# A1-A2_Switches_new.net
KiCad netlist of a schematic drawn in Altium Designer
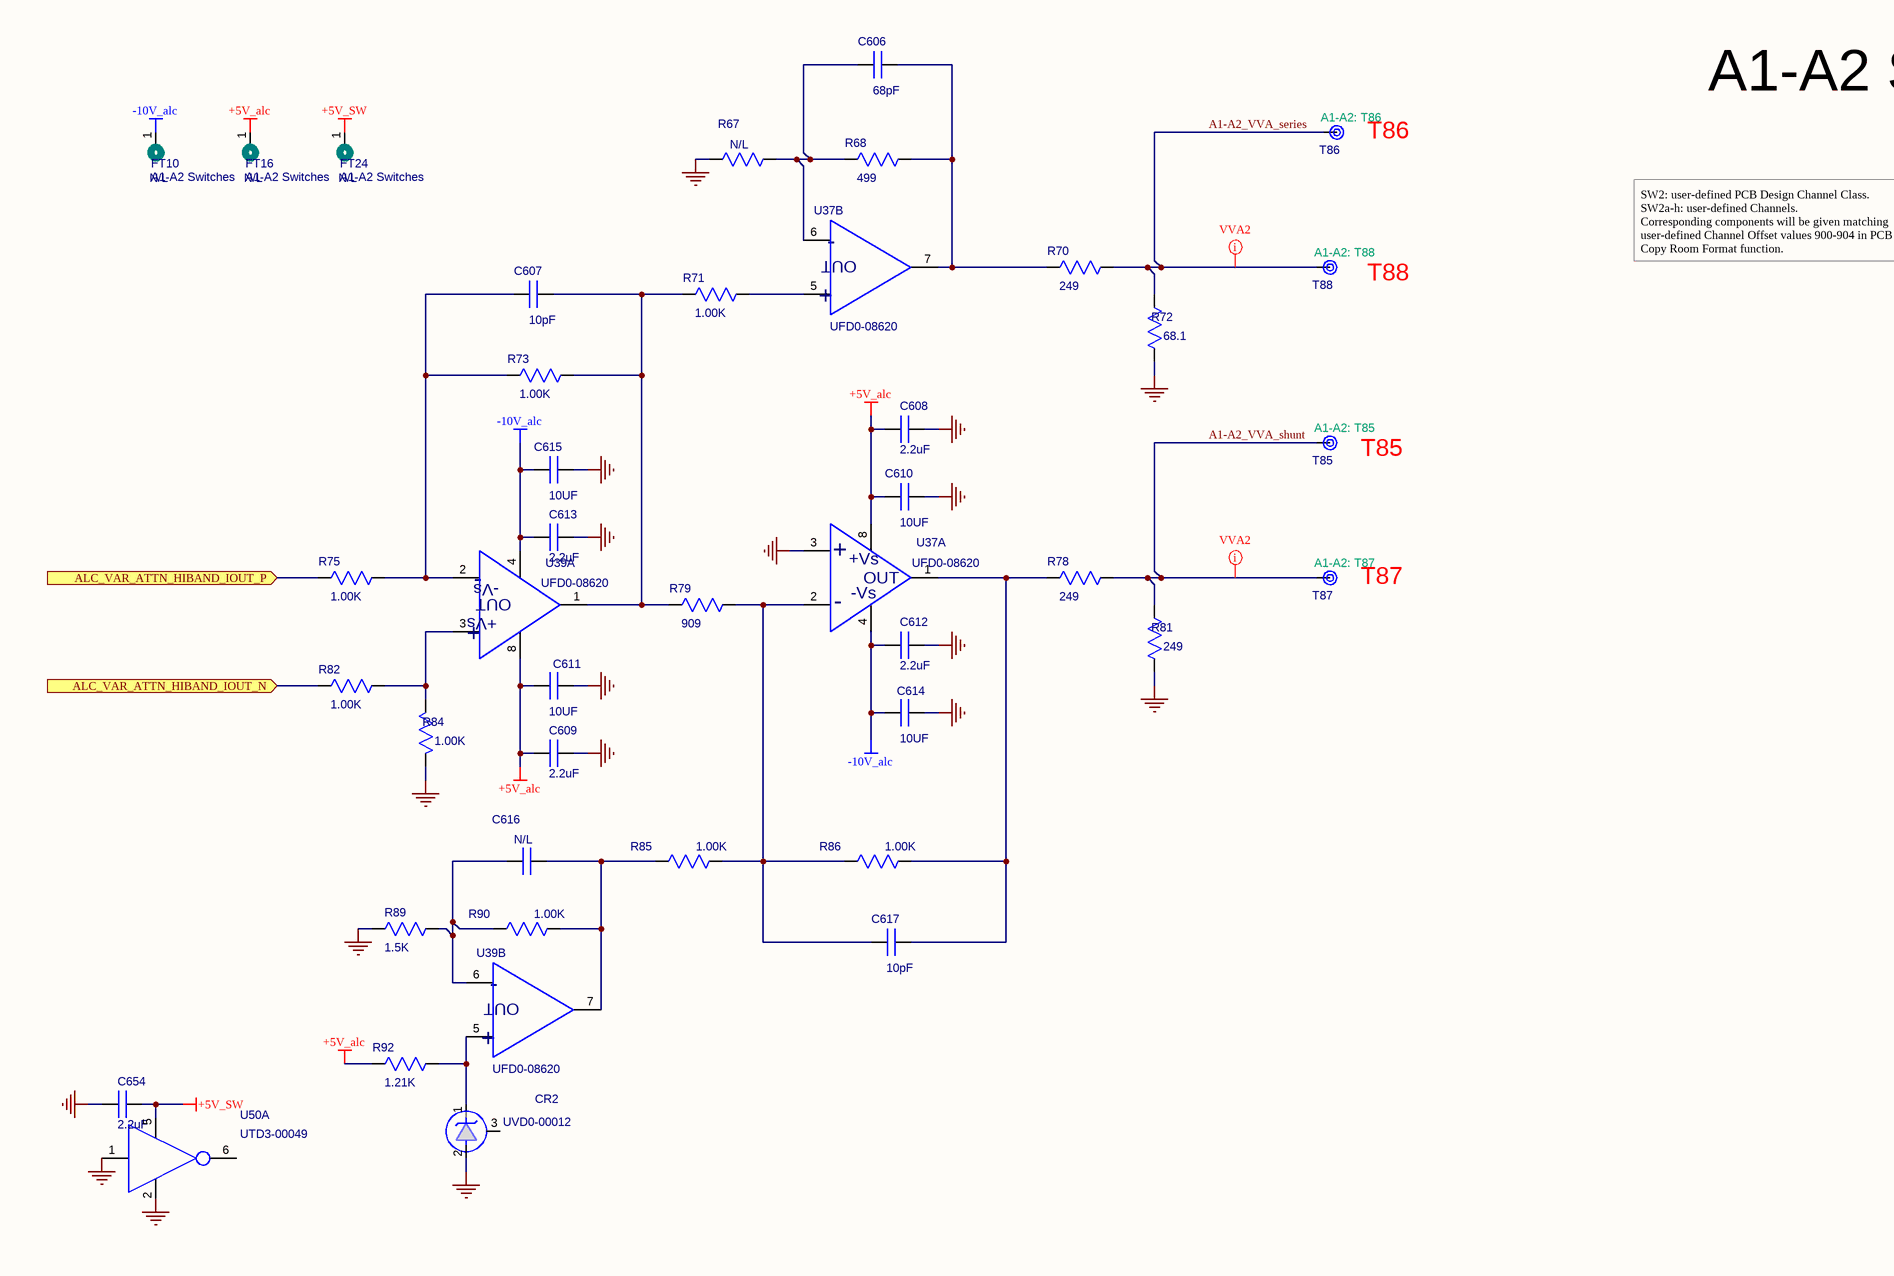
[diagram p0: A1-A2 Switches new.SchDoc, top left]
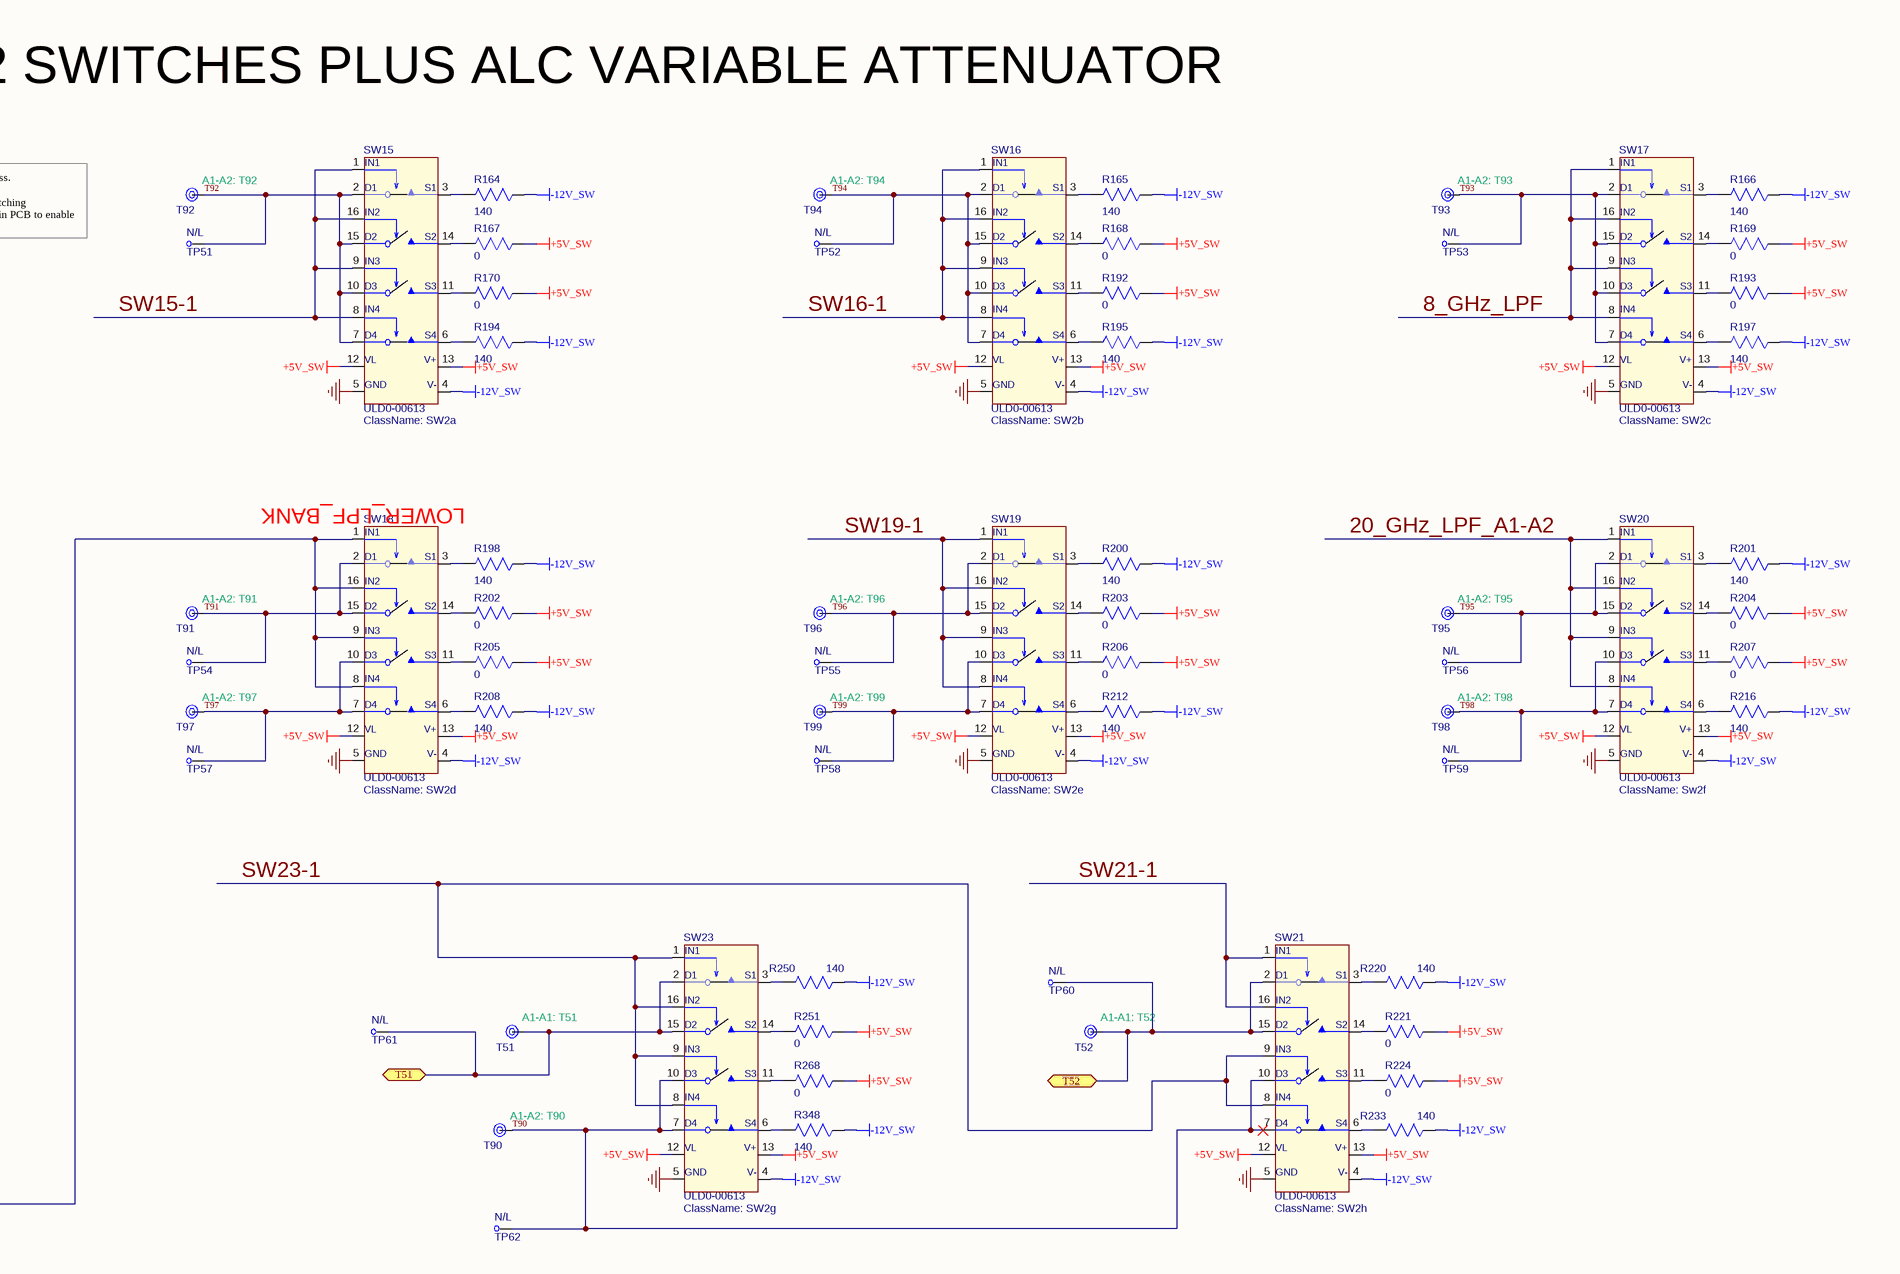
[diagram p1: A1-A2 Switches new.SchDoc, top right]
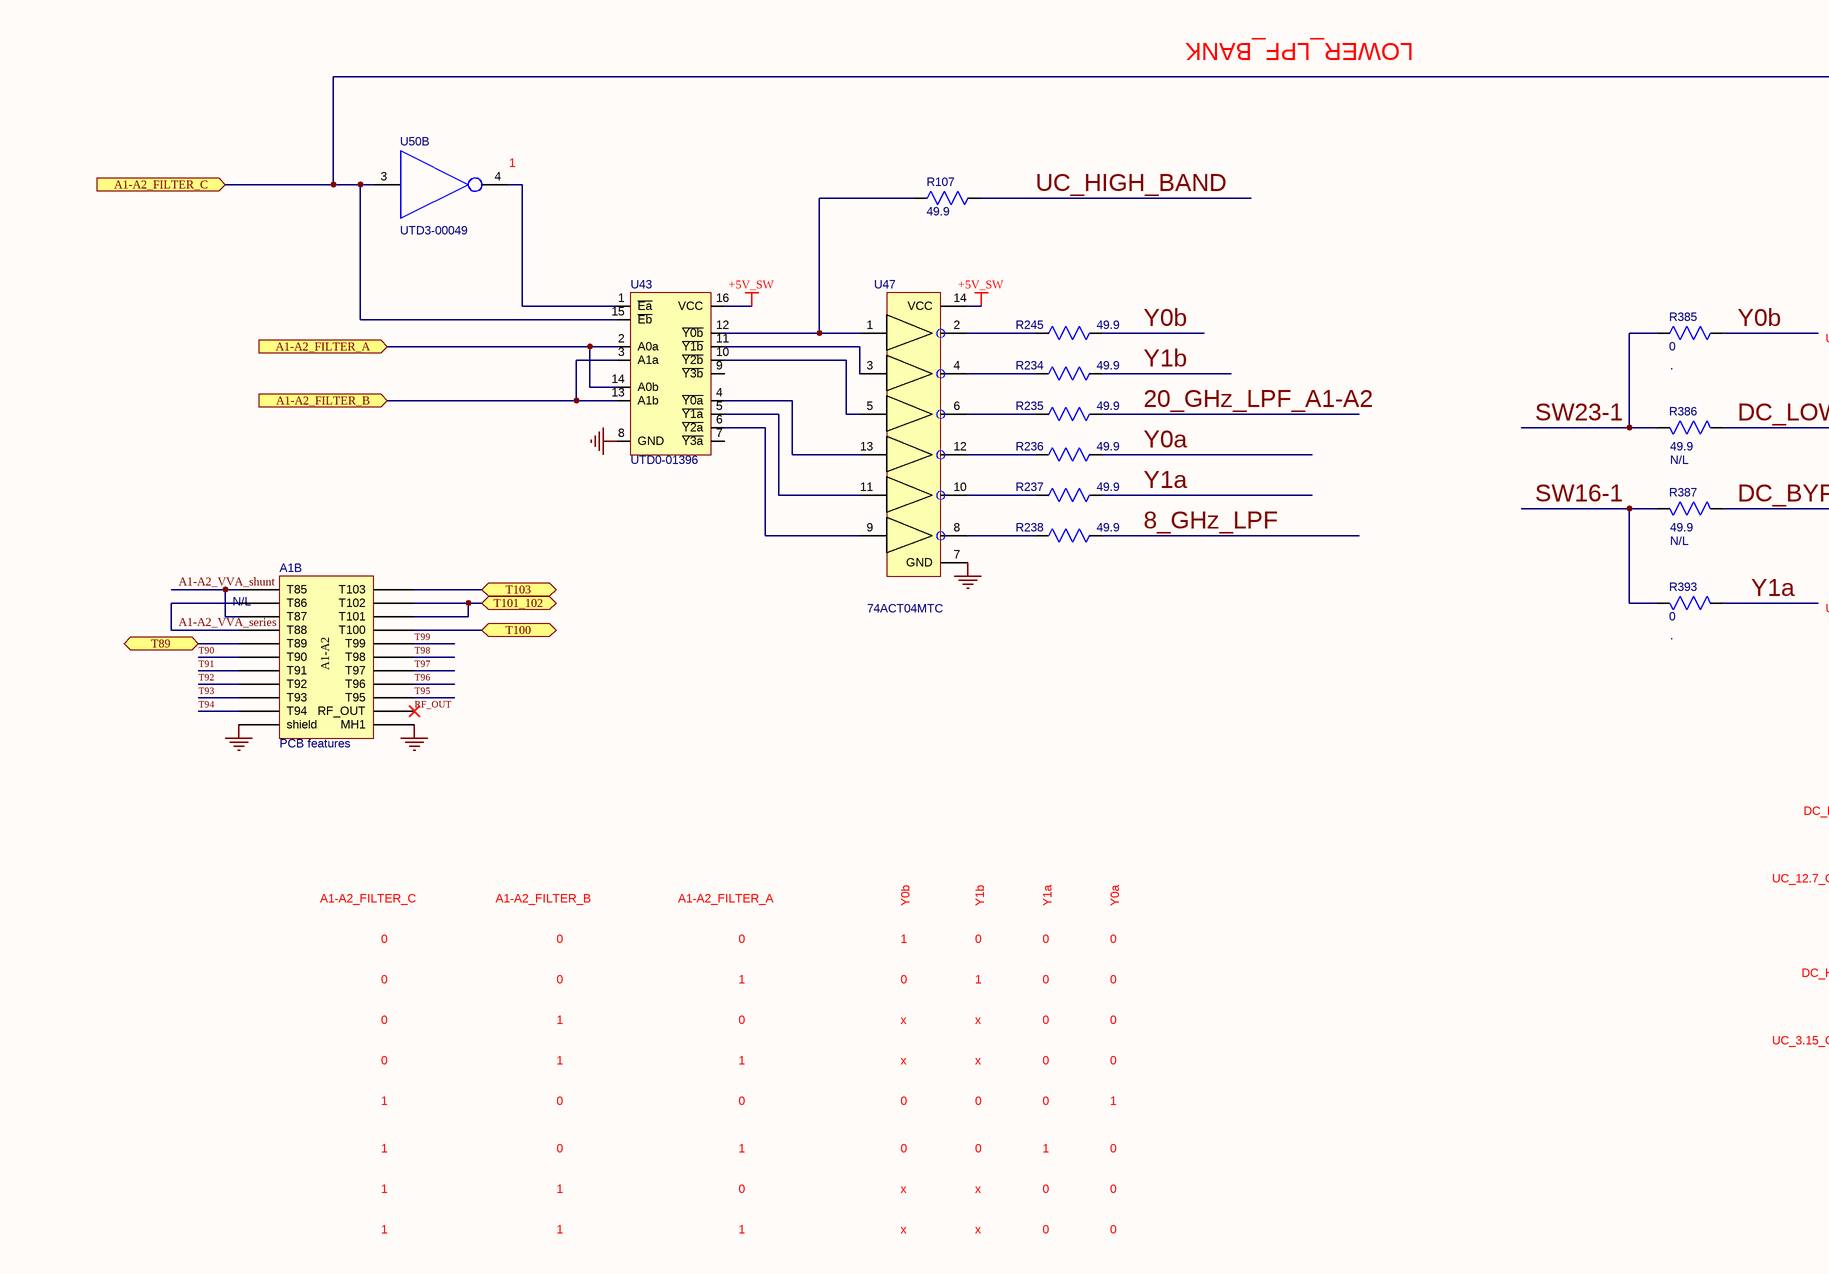
[diagram p2: A1-A2 Switches new.SchDoc, bottom left]
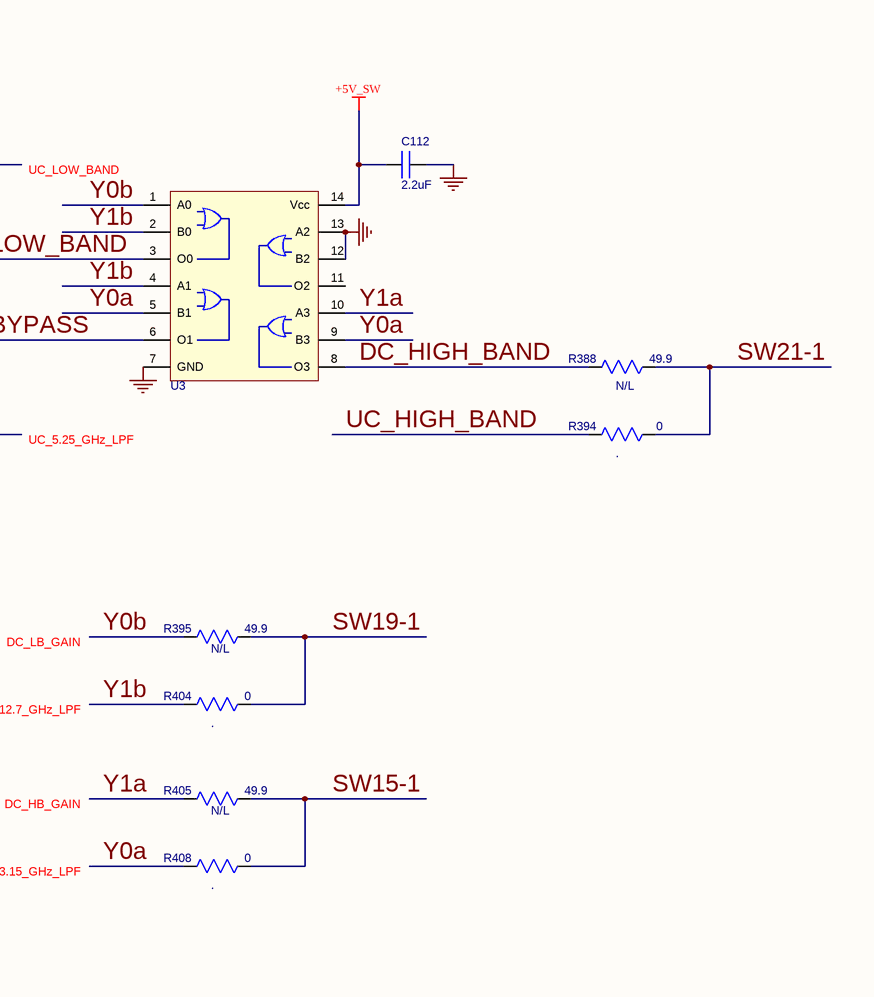
[diagram p3: A1-A2 Switches new.SchDoc, bottom right]

(export (version "E")
  (design (tool "Eeschema 10.0.6"))
  (components
    (comp (ref "A1")
      (value "PCB features")
      (footprint "Hydra_A1_output_modules")
      (description "Hydra A1 output modules (PCB features)")
      (fields (field (name "NOLOAD") "N/L") (field (name "APPROVED") "*"))
      (libsource (lib "Giga-tronics") (part "Hydra A1 output modules"))
    )
    (comp (ref "C112")
      (value "2.2uF")
      (footprint "CAP-0603-H035-N")
      (description "CAP,CHP,2.2UF,10%,X5R;16V")
      (fields (field (name "APPROVED") "CL"))
      (libsource (lib "Giga-tronics") (part "CK45-05220"))
    )
    (comp (ref "C606")
      (value "68pF")
      (footprint "CAP-0402-N")
      (description "68pF;5%;COG;50V;CHIP;0402")
      (fields (field (name "APPROVED") "CL"))
      (libsource (lib "Giga-tronics") (part "CK40-00680"))
    )
    (comp (ref "C607")
      (value "10pF")
      (footprint "CAP-0402-N")
      (description "10 PF;5%;COG;>50V;CHIP;0402")
      (fields (field (name "APPROVED") "CL"))
      (libsource (lib "Giga-tronics") (part "CK40-00100"))
    )
    (comp (ref "C608")
      (value "2.2uF")
      (footprint "CAP-0603-H035-N")
      (description "CAP,CHP,2.2UF,10%,X5R;16V")
      (fields (field (name "APPROVED") "CL"))
      (libsource (lib "Giga-tronics") (part "CK45-05220"))
    )
    (comp (ref "C609")
      (value "2.2uF")
      (footprint "CAP-0603-H035-N")
      (description "CAP,CHP,2.2UF,10%,X5R;16V")
      (fields (field (name "APPROVED") "CL"))
      (libsource (lib "Giga-tronics") (part "CK45-05220"))
    )
    (comp (ref "C610")
      (value "10UF")
      (footprint "CAP-1210-N")
      (description "10uF 10% X7R CERAMIC 16V 1210 CHIP")
      (fields (field (name "APPROVED") "XiaoXiao"))
      (libsource (lib "Giga-tronics") (part "CK60-06100"))
    )
    (comp (ref "C611")
      (value "10UF")
      (footprint "CAP-1210-N")
      (description "10uF 10% X7R CERAMIC 16V 1210 CHIP")
      (fields (field (name "APPROVED") "XiaoXiao"))
      (libsource (lib "Giga-tronics") (part "CK60-06100"))
    )
    (comp (ref "C612")
      (value "2.2uF")
      (footprint "CAP-0603-H035-N")
      (description "CAP,CHP,2.2UF,10%,X5R;16V")
      (fields (field (name "APPROVED") "CL"))
      (libsource (lib "Giga-tronics") (part "CK45-05220"))
    )
    (comp (ref "C613")
      (value "2.2uF")
      (footprint "CAP-0603-H035-N")
      (description "CAP,CHP,2.2UF,10%,X5R;16V")
      (fields (field (name "APPROVED") "CL"))
      (libsource (lib "Giga-tronics") (part "CK45-05220"))
    )
    (comp (ref "C614")
      (value "10UF")
      (footprint "CAP-1210-N")
      (description "10uF 10% X7R CERAMIC 16V 1210 CHIP")
      (fields (field (name "APPROVED") "XiaoXiao"))
      (libsource (lib "Giga-tronics") (part "CK60-06100"))
    )
    (comp (ref "C615")
      (value "10UF")
      (footprint "CAP-1210-N")
      (description "10uF 10% X7R CERAMIC 16V 1210 CHIP")
      (fields (field (name "APPROVED") "XiaoXiao"))
      (libsource (lib "Giga-tronics") (part "CK60-06100"))
    )
    (comp (ref "C616")
      (value "2.2pF;5%;COG;50V;CHIP;0402")
      (footprint "CAP-0402-N")
      (fields (field (name "NOLOAD") "N/L") (field (name "APPROVED") "CL"))
      (libsource (lib "Giga-tronics") (part "CK40-00022"))
    )
    (comp (ref "C617")
      (value "10pF")
      (footprint "CAP-0402-N")
      (description "10 PF;5%;COG;>50V;CHIP;0402")
      (fields (field (name "APPROVED") "CL"))
      (libsource (lib "Giga-tronics") (part "CK40-00100"))
    )
    (comp (ref "C654")
      (value "2.2uF")
      (footprint "CAP-0603-H035-N")
      (description "CAP,CHP,2.2UF,10%,X5R;16V")
      (fields (field (name "APPROVED") "CL"))
      (libsource (lib "Giga-tronics") (part "CK45-05220"))
    )
    (comp (ref "CR2")
      (value "VREF;1.235V;+/-4MV;.2MV 0-70 DEG C;SOT-23")
      (footprint "SOT23-N")
      (fields (field (name "G_PN") "UVD0-00012") (field (name "APPROVED") "CL"))
      (libsource (lib "Giga-tronics") (part "UVD0-00012"))
    )
    (comp (ref "FT10")
      (value "A1-A2 Switches")
      (footprint "FromToNode_ML2")
      (fields (field (name "NOLOAD") "N/L") (field (name "APPROVED") "*"))
      (libsource (lib "Giga-tronics") (part "FromToNode"))
    )
    (comp (ref "FT16")
      (value "A1-A2 Switches")
      (footprint "FromToNode_ML2")
      (fields (field (name "NOLOAD") "N/L") (field (name "APPROVED") "*"))
      (libsource (lib "Giga-tronics") (part "FromToNode"))
    )
    (comp (ref "FT24")
      (value "A1-A2 Switches")
      (footprint "FromToNode_ML2")
      (fields (field (name "NOLOAD") "N/L") (field (name "APPROVED") "*"))
      (libsource (lib "Giga-tronics") (part "FromToNode"))
    )
    (comp (ref "R67")
      (value "32.4K OHMS;.06W;1%;200PPM;FILM;CHIP;0402")
      (footprint "RES-0402-N")
      (fields (field (name "NOLOAD") "N/L") (field (name "APPROVED") "CL"))
      (libsource (lib "Giga-tronics") (part "RK35-23240"))
    )
    (comp (ref "R68")
      (value "499")
      (footprint "RES-0402-N")
      (description "499 OHMS; 1%; .1W; 100PPM; FILM; CHIP; 0402")
      (fields (field (name "APPROVED") "CL"))
      (libsource (lib "Giga-tronics") (part "RK35-04990"))
    )
    (comp (ref "R70")
      (value "249")
      (footprint "RES-0402-N")
      (description "249 OHMS; 1%; .1W; 100PPM; FILM; CHIP; 0402")
      (fields (field (name "APPROVED") "CL"))
      (libsource (lib "Giga-tronics") (part "RK35-02490"))
    )
    (comp (ref "R71")
      (value "1.00K")
      (footprint "RES-0402-N")
      (description "1.0K OHMS;.06W;1%;200PPM;FILM;CHIP;0402")
      (fields (field (name "APPROVED") "CL"))
      (libsource (lib "Giga-tronics") (part "RK35-11000"))
    )
    (comp (ref "R72")
      (value "68.1")
      (footprint "RES-0402-N")
      (description "68.1 OHMS;.06W;1%;200PPM;FILM;CHIP;0402")
      (fields (field (name "APPROVED") "CL"))
      (libsource (lib "Giga-tronics") (part "RK35-00681"))
    )
    (comp (ref "R73")
      (value "1.00K")
      (footprint "RES-0402-N")
      (description "1.0K OHMS;.06W;1%;200PPM;FILM;CHIP;0402")
      (fields (field (name "APPROVED") "CL"))
      (libsource (lib "Giga-tronics") (part "RK35-11000"))
    )
    (comp (ref "R75")
      (value "1.00K")
      (footprint "RES-0402-N")
      (description "1.0K OHMS;.06W;1%;200PPM;FILM;CHIP;0402")
      (fields (field (name "APPROVED") "CL"))
      (libsource (lib "Giga-tronics") (part "RK35-11000"))
    )
    (comp (ref "R78")
      (value "249")
      (footprint "RES-0402-N")
      (description "249 OHMS; 1%; .1W; 100PPM; FILM; CHIP; 0402")
      (fields (field (name "APPROVED") "CL"))
      (libsource (lib "Giga-tronics") (part "RK35-02490"))
    )
    (comp (ref "R79")
      (value "909")
      (footprint "RES-0402-N")
      (description "909 OHMS; 1%; .1W; 100PPM; FILM; CHIP; 0402")
      (fields (field (name "APPROVED") "CL"))
      (libsource (lib "Giga-tronics") (part "RK35-09090"))
    )
    (comp (ref "R81")
      (value "249")
      (footprint "RES-0402-N")
      (description "249 OHMS; 1%; .1W; 100PPM; FILM; CHIP; 0402")
      (fields (field (name "APPROVED") "CL"))
      (libsource (lib "Giga-tronics") (part "RK35-02490"))
    )
    (comp (ref "R82")
      (value "1.00K")
      (footprint "RES-0402-N")
      (description "1.0K OHMS;.06W;1%;200PPM;FILM;CHIP;0402")
      (fields (field (name "APPROVED") "CL"))
      (libsource (lib "Giga-tronics") (part "RK35-11000"))
    )
    (comp (ref "R84")
      (value "1.00K")
      (footprint "RES-0402-N")
      (description "1.0K OHMS;.06W;1%;200PPM;FILM;CHIP;0402")
      (fields (field (name "APPROVED") "CL"))
      (libsource (lib "Giga-tronics") (part "RK35-11000"))
    )
    (comp (ref "R85")
      (value "1.00K")
      (footprint "RES-0402-N")
      (description "1.0K OHMS;.06W;1%;200PPM;FILM;CHIP;0402")
      (fields (field (name "APPROVED") "CL"))
      (libsource (lib "Giga-tronics") (part "RK35-11000"))
    )
    (comp (ref "R86")
      (value "1.00K")
      (footprint "RES-0402-N")
      (description "1.0K OHMS;.06W;1%;200PPM;FILM;CHIP;0402")
      (fields (field (name "APPROVED") "CL"))
      (libsource (lib "Giga-tronics") (part "RK35-11000"))
    )
    (comp (ref "R89")
      (value "1.5K")
      (footprint "RES-0402-N")
      (description "1.50K Ohms;.06W;1%;±100PPM;CHIP RES;0402")
      (fields (field (name "APPROVED") "CL"))
      (libsource (lib "Giga-tronics") (part "RK35-11500"))
    )
    (comp (ref "R90")
      (value "1.00K")
      (footprint "RES-0402-N")
      (description "1.0K OHMS;.06W;1%;200PPM;FILM;CHIP;0402")
      (fields (field (name "APPROVED") "CL"))
      (libsource (lib "Giga-tronics") (part "RK35-11000"))
    )
    (comp (ref "R92")
      (value "1.21K")
      (footprint "RES-0402-N")
      (description "1.21K OHMS;.06W;1%;200PPM;FILM;CHIP;0402")
      (fields (field (name "APPROVED") "CL"))
      (libsource (lib "Giga-tronics") (part "RK35-11210"))
    )
    (comp (ref "R107")
      (value "49.9")
      (footprint "RES-0402-N")
      (description "49.9 OHMS;.06W;1%;200PPM;FILM;CHIP;0402")
      (fields (field (name "APPROVED") "CL"))
      (libsource (lib "Giga-tronics") (part "RK35-00499"))
    )
    (comp (ref "R164")
      (value "140")
      (footprint "RES-0402-N")
      (description "140 OHMS; 1%; .1W; 100PPM; FILM; CHIP; 0402")
      (fields (field (name "APPROVED") "CL"))
      (libsource (lib "Giga-tronics") (part "RK35-01400"))
    )
    (comp (ref "R165")
      (value "140")
      (footprint "RES-0402-N")
      (description "140 OHMS; 1%; .1W; 100PPM; FILM; CHIP; 0402")
      (fields (field (name "APPROVED") "CL"))
      (libsource (lib "Giga-tronics") (part "RK35-01400"))
    )
    (comp (ref "R166")
      (value "140")
      (footprint "RES-0402-N")
      (description "140 OHMS; 1%; .1W; 100PPM; FILM; CHIP; 0402")
      (fields (field (name "APPROVED") "CL"))
      (libsource (lib "Giga-tronics") (part "RK35-01400"))
    )
    (comp (ref "R167")
      (value "0")
      (footprint "RES-0603-N")
      (description "JUMPER;.05 OHMS MAX;1A MAX;0603")
      (fields (field (name "APPROVED") "CL"))
      (libsource (lib "Giga-tronics") (part "RK40-00000"))
    )
    (comp (ref "R168")
      (value "0")
      (footprint "RES-0603-N")
      (description "JUMPER;.05 OHMS MAX;1A MAX;0603")
      (fields (field (name "APPROVED") "CL"))
      (libsource (lib "Giga-tronics") (part "RK40-00000"))
    )
    (comp (ref "R169")
      (value "0")
      (footprint "RES-0603-N")
      (description "JUMPER;.05 OHMS MAX;1A MAX;0603")
      (fields (field (name "APPROVED") "CL"))
      (libsource (lib "Giga-tronics") (part "RK40-00000"))
    )
    (comp (ref "R170")
      (value "0")
      (footprint "RES-0603-N")
      (description "JUMPER;.05 OHMS MAX;1A MAX;0603")
      (fields (field (name "APPROVED") "CL"))
      (libsource (lib "Giga-tronics") (part "RK40-00000"))
    )
    (comp (ref "R192")
      (value "0")
      (footprint "RES-0603-N")
      (description "JUMPER;.05 OHMS MAX;1A MAX;0603")
      (fields (field (name "APPROVED") "CL"))
      (libsource (lib "Giga-tronics") (part "RK40-00000"))
    )
    (comp (ref "R193")
      (value "0")
      (footprint "RES-0603-N")
      (description "JUMPER;.05 OHMS MAX;1A MAX;0603")
      (fields (field (name "APPROVED") "CL"))
      (libsource (lib "Giga-tronics") (part "RK40-00000"))
    )
    (comp (ref "R194")
      (value "140")
      (footprint "RES-0402-N")
      (description "140 OHMS; 1%; .1W; 100PPM; FILM; CHIP; 0402")
      (fields (field (name "APPROVED") "CL"))
      (libsource (lib "Giga-tronics") (part "RK35-01400"))
    )
    (comp (ref "R195")
      (value "140")
      (footprint "RES-0402-N")
      (description "140 OHMS; 1%; .1W; 100PPM; FILM; CHIP; 0402")
      (fields (field (name "APPROVED") "CL"))
      (libsource (lib "Giga-tronics") (part "RK35-01400"))
    )
    (comp (ref "R197")
      (value "140")
      (footprint "RES-0402-N")
      (description "140 OHMS; 1%; .1W; 100PPM; FILM; CHIP; 0402")
      (fields (field (name "APPROVED") "CL"))
      (libsource (lib "Giga-tronics") (part "RK35-01400"))
    )
    (comp (ref "R198")
      (value "140")
      (footprint "RES-0402-N")
      (description "140 OHMS; 1%; .1W; 100PPM; FILM; CHIP; 0402")
      (fields (field (name "APPROVED") "CL"))
      (libsource (lib "Giga-tronics") (part "RK35-01400"))
    )
    (comp (ref "R200")
      (value "140")
      (footprint "RES-0402-N")
      (description "140 OHMS; 1%; .1W; 100PPM; FILM; CHIP; 0402")
      (fields (field (name "APPROVED") "CL"))
      (libsource (lib "Giga-tronics") (part "RK35-01400"))
    )
    (comp (ref "R201")
      (value "140")
      (footprint "RES-0402-N")
      (description "140 OHMS; 1%; .1W; 100PPM; FILM; CHIP; 0402")
      (fields (field (name "APPROVED") "CL"))
      (libsource (lib "Giga-tronics") (part "RK35-01400"))
    )
    (comp (ref "R202")
      (value "0")
      (footprint "RES-0603-N")
      (description "JUMPER;.05 OHMS MAX;1A MAX;0603")
      (fields (field (name "APPROVED") "CL"))
      (libsource (lib "Giga-tronics") (part "RK40-00000"))
    )
    (comp (ref "R203")
      (value "0")
      (footprint "RES-0603-N")
      (description "JUMPER;.05 OHMS MAX;1A MAX;0603")
      (fields (field (name "APPROVED") "CL"))
      (libsource (lib "Giga-tronics") (part "RK40-00000"))
    )
    (comp (ref "R204")
      (value "0")
      (footprint "RES-0603-N")
      (description "JUMPER;.05 OHMS MAX;1A MAX;0603")
      (fields (field (name "APPROVED") "CL"))
      (libsource (lib "Giga-tronics") (part "RK40-00000"))
    )
    (comp (ref "R205")
      (value "0")
      (footprint "RES-0603-N")
      (description "JUMPER;.05 OHMS MAX;1A MAX;0603")
      (fields (field (name "APPROVED") "CL"))
      (libsource (lib "Giga-tronics") (part "RK40-00000"))
    )
    (comp (ref "R206")
      (value "0")
      (footprint "RES-0603-N")
      (description "JUMPER;.05 OHMS MAX;1A MAX;0603")
      (fields (field (name "APPROVED") "CL"))
      (libsource (lib "Giga-tronics") (part "RK40-00000"))
    )
    (comp (ref "R207")
      (value "0")
      (footprint "RES-0603-N")
      (description "JUMPER;.05 OHMS MAX;1A MAX;0603")
      (fields (field (name "APPROVED") "CL"))
      (libsource (lib "Giga-tronics") (part "RK40-00000"))
    )
    (comp (ref "R208")
      (value "140")
      (footprint "RES-0402-N")
      (description "140 OHMS; 1%; .1W; 100PPM; FILM; CHIP; 0402")
      (fields (field (name "APPROVED") "CL"))
      (libsource (lib "Giga-tronics") (part "RK35-01400"))
    )
    (comp (ref "R212")
      (value "140")
      (footprint "RES-0402-N")
      (description "140 OHMS; 1%; .1W; 100PPM; FILM; CHIP; 0402")
      (fields (field (name "APPROVED") "CL"))
      (libsource (lib "Giga-tronics") (part "RK35-01400"))
    )
    (comp (ref "R216")
      (value "140")
      (footprint "RES-0402-N")
      (description "140 OHMS; 1%; .1W; 100PPM; FILM; CHIP; 0402")
      (fields (field (name "APPROVED") "CL"))
      (libsource (lib "Giga-tronics") (part "RK35-01400"))
    )
    (comp (ref "R220")
      (value "140")
      (footprint "RES-0603-N")
      (description "140 OHMS;.1W;1%;200PPM;FILM;CHIP;0603")
      (fields (field (name "APPROVED") "CL"))
      (libsource (lib "Giga-tronics") (part "RK41-01400"))
    )
    (comp (ref "R221")
      (value "0")
      (footprint "RES-0603-N")
      (description "JUMPER;.05 OHMS MAX;1A MAX;0603")
      (fields (field (name "APPROVED") "CL"))
      (libsource (lib "Giga-tronics") (part "RK40-00000"))
    )
    (comp (ref "R224")
      (value "0")
      (footprint "RES-0603-N")
      (description "JUMPER;.05 OHMS MAX;1A MAX;0603")
      (fields (field (name "APPROVED") "CL"))
      (libsource (lib "Giga-tronics") (part "RK40-00000"))
    )
    (comp (ref "R233")
      (value "140")
      (footprint "RES-0603-N")
      (description "140 OHMS;.1W;1%;200PPM;FILM;CHIP;0603")
      (fields (field (name "APPROVED") "CL"))
      (libsource (lib "Giga-tronics") (part "RK41-01400"))
    )
    (comp (ref "R234")
      (value "49.9")
      (footprint "RES-0402-N")
      (description "49.9 OHMS;.06W;1%;200PPM;FILM;CHIP;0402")
      (fields (field (name "APPROVED") "CL"))
      (libsource (lib "Giga-tronics") (part "RK35-00499"))
    )
    (comp (ref "R235")
      (value "49.9")
      (footprint "RES-0402-N")
      (description "49.9 OHMS;.06W;1%;200PPM;FILM;CHIP;0402")
      (fields (field (name "APPROVED") "CL"))
      (libsource (lib "Giga-tronics") (part "RK35-00499"))
    )
    (comp (ref "R236")
      (value "49.9")
      (footprint "RES-0402-N")
      (description "49.9 OHMS;.06W;1%;200PPM;FILM;CHIP;0402")
      (fields (field (name "APPROVED") "CL"))
      (libsource (lib "Giga-tronics") (part "RK35-00499"))
    )
    (comp (ref "R237")
      (value "49.9")
      (footprint "RES-0402-N")
      (description "49.9 OHMS;.06W;1%;200PPM;FILM;CHIP;0402")
      (fields (field (name "APPROVED") "CL"))
      (libsource (lib "Giga-tronics") (part "RK35-00499"))
    )
    (comp (ref "R238")
      (value "49.9")
      (footprint "RES-0402-N")
      (description "49.9 OHMS;.06W;1%;200PPM;FILM;CHIP;0402")
      (fields (field (name "APPROVED") "CL"))
      (libsource (lib "Giga-tronics") (part "RK35-00499"))
    )
    (comp (ref "R245")
      (value "49.9")
      (footprint "RES-0402-N")
      (description "49.9 OHMS;.06W;1%;200PPM;FILM;CHIP;0402")
      (fields (field (name "APPROVED") "CL"))
      (libsource (lib "Giga-tronics") (part "RK35-00499"))
    )
    (comp (ref "R250")
      (value "140")
      (footprint "RES-0603-N")
      (description "140 OHMS;.1W;1%;200PPM;FILM;CHIP;0603")
      (fields (field (name "APPROVED") "CL"))
      (libsource (lib "Giga-tronics") (part "RK41-01400"))
    )
    (comp (ref "R251")
      (value "0")
      (footprint "RES-0603-N")
      (description "JUMPER;.05 OHMS MAX;1A MAX;0603")
      (fields (field (name "APPROVED") "CL"))
      (libsource (lib "Giga-tronics") (part "RK40-00000"))
    )
    (comp (ref "R268")
      (value "0")
      (footprint "RES-0603-N")
      (description "JUMPER;.05 OHMS MAX;1A MAX;0603")
      (fields (field (name "APPROVED") "CL"))
      (libsource (lib "Giga-tronics") (part "RK40-00000"))
    )
    (comp (ref "R348")
      (value "140")
      (footprint "RES-0402-N")
      (description "140 OHMS; 1%; .1W; 100PPM; FILM; CHIP; 0402")
      (fields (field (name "APPROVED") "CL"))
      (libsource (lib "Giga-tronics") (part "RK35-01400"))
    )
    (comp (ref "R385")
      (value "UC_LOW_BAND")
      (footprint "RES-0402-N")
      (description "JUMPER;0 OHMS;SMT;0402")
      (fields (field (name "NOLOAD") ".") (field (name "ALTIUM_VALUE") "0") (field (name "APPROVED") "CL"))
      (libsource (lib "Giga-tronics") (part "RK35-00000"))
    )
    (comp (ref "R386")
      (value "49.9")
      (footprint "RES-0402-N")
      (description "49.9 OHMS;.06W;1%;200PPM;FILM;CHIP;0402")
      (fields
        (field (name "NOLOAD") "N/L")
        (field (name "Comment") "DC_LOW_BAND")
        (field (name "APPROVED") "CL")
      )
      (libsource (lib "Giga-tronics") (part "RK35-00499"))
    )
    (comp (ref "R387")
      (value "49.9")
      (footprint "RES-0402-N")
      (description "49.9 OHMS;.06W;1%;200PPM;FILM;CHIP;0402")
      (fields
        (field (name "NOLOAD") "N/L")
        (field (name "Comment") "DC_BYPASS")
        (field (name "APPROVED") "CL")
      )
      (libsource (lib "Giga-tronics") (part "RK35-00499"))
    )
    (comp (ref "R388")
      (value "49.9")
      (footprint "RES-0402-N")
      (description "49.9 OHMS;.06W;1%;200PPM;FILM;CHIP;0402")
      (fields
        (field (name "NOLOAD") "N/L")
        (field (name "Comment") "DC_HIGH_BAND")
        (field (name "APPROVED") "CL")
      )
      (libsource (lib "Giga-tronics") (part "RK35-00499"))
    )
    (comp (ref "R393")
      (value "UC_5.25_GHz_LPF")
      (footprint "RES-0402-N")
      (description "JUMPER;0 OHMS;SMT;0402")
      (fields (field (name "NOLOAD") ".") (field (name "ALTIUM_VALUE") "0") (field (name "APPROVED") "CL"))
      (libsource (lib "Giga-tronics") (part "RK35-00000"))
    )
    (comp (ref "R394")
      (value "0")
      (footprint "RES-0402-N")
      (description "JUMPER;0 OHMS;SMT;0402")
      (fields
        (field (name "NOLOAD") ".")
        (field (name "Comment") "UC_HIGH_BAND")
        (field (name "APPROVED") "CL")
      )
      (libsource (lib "Giga-tronics") (part "RK35-00000"))
    )
    (comp (ref "R395")
      (value "DC_LB_GAIN")
      (footprint "RES-0402-N")
      (description "49.9 OHMS;.06W;1%;200PPM;FILM;CHIP;0402")
      (fields
        (field (name "NOLOAD") "N/L")
        (field (name "ALTIUM_VALUE") "49.9")
        (field (name "APPROVED") "CL")
      )
      (libsource (lib "Giga-tronics") (part "RK35-00499"))
    )
    (comp (ref "R404")
      (value "UC_12.7_GHz_LPF")
      (footprint "RES-0402-N")
      (description "JUMPER;0 OHMS;SMT;0402")
      (fields (field (name "NOLOAD") ".") (field (name "ALTIUM_VALUE") "0") (field (name "APPROVED") "CL"))
      (libsource (lib "Giga-tronics") (part "RK35-00000"))
    )
    (comp (ref "R405")
      (value "DC_HB_GAIN")
      (footprint "RES-0402-N")
      (description "49.9 OHMS;.06W;1%;200PPM;FILM;CHIP;0402")
      (fields
        (field (name "NOLOAD") "N/L")
        (field (name "ALTIUM_VALUE") "49.9")
        (field (name "APPROVED") "CL")
      )
      (libsource (lib "Giga-tronics") (part "RK35-00499"))
    )
    (comp (ref "R408")
      (value "UC_3.15_GHz_LPF")
      (footprint "RES-0402-N")
      (description "JUMPER;0 OHMS;SMT;0402")
      (fields (field (name "NOLOAD") ".") (field (name "ALTIUM_VALUE") "0") (field (name "APPROVED") "CL"))
      (libsource (lib "Giga-tronics") (part "RK35-00000"))
    )
    (comp (ref "SW15")
      (value "QUAD SPST ANALOG SW;200NS;45 OHM;SO-16")
      (footprint "SOIC-16_Vishay")
      (fields
        (field (name "G_PN") "ULD0-00613")
        (field (name "CLASSNAME") "SW2a")
        (field (name "APPROVED") "NM")
      )
      (libsource (lib "Giga-tronics") (part "ULD0-00613_1"))
    )
    (comp (ref "SW16")
      (value "QUAD SPST ANALOG SW;200NS;45 OHM;SO-16")
      (footprint "SOIC-16_Vishay")
      (fields
        (field (name "G_PN") "ULD0-00613")
        (field (name "CLASSNAME") "SW2b")
        (field (name "APPROVED") "NM")
      )
      (libsource (lib "Giga-tronics") (part "ULD0-00613_1"))
    )
    (comp (ref "SW17")
      (value "QUAD SPST ANALOG SW;200NS;45 OHM;SO-16")
      (footprint "SOIC-16_Vishay")
      (fields
        (field (name "G_PN") "ULD0-00613")
        (field (name "CLASSNAME") "SW2c")
        (field (name "APPROVED") "NM")
      )
      (libsource (lib "Giga-tronics") (part "ULD0-00613_1"))
    )
    (comp (ref "SW18")
      (value "QUAD SPST ANALOG SW;200NS;45 OHM;SO-16")
      (footprint "SOIC-16_Vishay")
      (fields
        (field (name "G_PN") "ULD0-00613")
        (field (name "CLASSNAME") "SW2d")
        (field (name "APPROVED") "NM")
      )
      (libsource (lib "Giga-tronics") (part "ULD0-00613_1"))
    )
    (comp (ref "SW19")
      (value "QUAD SPST ANALOG SW;200NS;45 OHM;SO-16")
      (footprint "SOIC-16_Vishay")
      (fields
        (field (name "G_PN") "ULD0-00613")
        (field (name "CLASSNAME") "SW2e")
        (field (name "APPROVED") "NM")
      )
      (libsource (lib "Giga-tronics") (part "ULD0-00613_1"))
    )
    (comp (ref "SW20")
      (value "QUAD SPST ANALOG SW;200NS;45 OHM;SO-16")
      (footprint "SOIC-16_Vishay")
      (fields
        (field (name "G_PN") "ULD0-00613")
        (field (name "CLASSNAME") "Sw2f")
        (field (name "APPROVED") "NM")
      )
      (libsource (lib "Giga-tronics") (part "ULD0-00613_1"))
    )
    (comp (ref "SW21")
      (value "QUAD SPST ANALOG SW;200NS;45 OHM;SO-16")
      (footprint "SOIC-16_Vishay")
      (fields
        (field (name "G_PN") "ULD0-00613")
        (field (name "CLASSNAME") "SW2h")
        (field (name "APPROVED") "NM")
      )
      (libsource (lib "Giga-tronics") (part "ULD0-00613_1"))
    )
    (comp (ref "SW23")
      (value "QUAD SPST ANALOG SW;200NS;45 OHM;SO-16")
      (footprint "SOIC-16_Vishay")
      (fields
        (field (name "G_PN") "ULD0-00613")
        (field (name "CLASSNAME") "SW2g")
        (field (name "APPROVED") "NM")
      )
      (libsource (lib "Giga-tronics") (part "ULD0-00613_1"))
    )
    (comp (ref "T51")
      (value "A1-A1: T51")
      (footprint "JIB0-11254")
      (description "SOCKET;SINGLE;.018-.040 ID X .254;OPEN;GLD")
      (fields (field (name "APPROVED") "NM"))
      (libsource (lib "Giga-tronics") (part "JIB0-11254"))
    )
    (comp (ref "T52")
      (value "A1-A1: T52")
      (footprint "JIB0-11254")
      (description "SOCKET;SINGLE;.018-.040 ID X .254;OPEN;GLD")
      (fields (field (name "APPROVED") "NM"))
      (libsource (lib "Giga-tronics") (part "JIB0-11254"))
    )
    (comp (ref "T85")
      (value "A1-A2: T85")
      (footprint "JIB0-11254")
      (description "SOCKET;SINGLE;.018-.040 ID X .254;OPEN;GLD")
      (fields (field (name "APPROVED") "NM"))
      (libsource (lib "Giga-tronics") (part "JIB0-11254"))
    )
    (comp (ref "T86")
      (value "A1-A2: T86")
      (footprint "JIB0-11254")
      (description "SOCKET;SINGLE;.018-.040 ID X .254;OPEN;GLD")
      (fields (field (name "APPROVED") "NM"))
      (libsource (lib "Giga-tronics") (part "JIB0-11254"))
    )
    (comp (ref "T87")
      (value "A1-A2: T87")
      (footprint "JIB0-11254")
      (description "SOCKET;SINGLE;.018-.040 ID X .254;OPEN;GLD")
      (fields (field (name "APPROVED") "NM"))
      (libsource (lib "Giga-tronics") (part "JIB0-11254"))
    )
    (comp (ref "T88")
      (value "A1-A2: T88")
      (footprint "JIB0-11254")
      (description "SOCKET;SINGLE;.018-.040 ID X .254;OPEN;GLD")
      (fields (field (name "APPROVED") "NM"))
      (libsource (lib "Giga-tronics") (part "JIB0-11254"))
    )
    (comp (ref "T90")
      (value "A1-A2: T90")
      (footprint "JIB0-11254")
      (description "SOCKET;SINGLE;.018-.040 ID X .254;OPEN;GLD")
      (fields (field (name "APPROVED") "NM"))
      (libsource (lib "Giga-tronics") (part "JIB0-11254"))
    )
    (comp (ref "T91")
      (value "A1-A2: T91")
      (footprint "JIB0-11254")
      (description "SOCKET;SINGLE;.018-.040 ID X .254;OPEN;GLD")
      (fields (field (name "APPROVED") "NM"))
      (libsource (lib "Giga-tronics") (part "JIB0-11254"))
    )
    (comp (ref "T92")
      (value "A1-A2: T92")
      (footprint "JIB0-11254")
      (description "SOCKET;SINGLE;.018-.040 ID X .254;OPEN;GLD")
      (fields (field (name "APPROVED") "NM"))
      (libsource (lib "Giga-tronics") (part "JIB0-11254"))
    )
    (comp (ref "T93")
      (value "A1-A2: T93")
      (footprint "JIB0-11254")
      (description "SOCKET;SINGLE;.018-.040 ID X .254;OPEN;GLD")
      (fields (field (name "APPROVED") "NM"))
      (libsource (lib "Giga-tronics") (part "JIB0-11254"))
    )
    (comp (ref "T94")
      (value "A1-A2: T94")
      (footprint "JIB0-11254")
      (description "SOCKET;SINGLE;.018-.040 ID X .254;OPEN;GLD")
      (fields (field (name "APPROVED") "NM"))
      (libsource (lib "Giga-tronics") (part "JIB0-11254"))
    )
    (comp (ref "T95")
      (value "A1-A2: T95")
      (footprint "JIB0-11254")
      (description "SOCKET;SINGLE;.018-.040 ID X .254;OPEN;GLD")
      (fields (field (name "APPROVED") "NM"))
      (libsource (lib "Giga-tronics") (part "JIB0-11254"))
    )
    (comp (ref "T96")
      (value "A1-A2: T96")
      (footprint "JIB0-11254")
      (description "SOCKET;SINGLE;.018-.040 ID X .254;OPEN;GLD")
      (fields (field (name "APPROVED") "NM"))
      (libsource (lib "Giga-tronics") (part "JIB0-11254"))
    )
    (comp (ref "T97")
      (value "A1-A2: T97")
      (footprint "JIB0-11254")
      (description "SOCKET;SINGLE;.018-.040 ID X .254;OPEN;GLD")
      (fields (field (name "APPROVED") "NM"))
      (libsource (lib "Giga-tronics") (part "JIB0-11254"))
    )
    (comp (ref "T98")
      (value "A1-A2: T98")
      (footprint "JIB0-11254")
      (description "SOCKET;SINGLE;.018-.040 ID X .254;OPEN;GLD")
      (fields (field (name "APPROVED") "NM"))
      (libsource (lib "Giga-tronics") (part "JIB0-11254"))
    )
    (comp (ref "T99")
      (value "A1-A2: T99")
      (footprint "JIB0-11254")
      (description "SOCKET;SINGLE;.018-.040 ID X .254;OPEN;GLD")
      (fields (field (name "APPROVED") "NM"))
      (libsource (lib "Giga-tronics") (part "JIB0-11254"))
    )
    (comp (ref "TP51")
      (value ".")
      (footprint "TP-060")
      (fields (field (name "NOLOAD") "N/L") (field (name "APPROVED") "NM"))
      (libsource (lib "Giga-tronics") (part "TP-060"))
    )
    (comp (ref "TP52")
      (value ".")
      (footprint "TP-060")
      (fields (field (name "NOLOAD") "N/L") (field (name "APPROVED") "NM"))
      (libsource (lib "Giga-tronics") (part "TP-060"))
    )
    (comp (ref "TP53")
      (value ".")
      (footprint "TP-060")
      (fields (field (name "NOLOAD") "N/L") (field (name "APPROVED") "NM"))
      (libsource (lib "Giga-tronics") (part "TP-060"))
    )
    (comp (ref "TP54")
      (value ".")
      (footprint "TP-060")
      (fields (field (name "NOLOAD") "N/L") (field (name "APPROVED") "NM"))
      (libsource (lib "Giga-tronics") (part "TP-060"))
    )
    (comp (ref "TP55")
      (value ".")
      (footprint "TP-060")
      (fields (field (name "NOLOAD") "N/L") (field (name "APPROVED") "NM"))
      (libsource (lib "Giga-tronics") (part "TP-060"))
    )
    (comp (ref "TP56")
      (value ".")
      (footprint "TP-060")
      (fields (field (name "NOLOAD") "N/L") (field (name "APPROVED") "NM"))
      (libsource (lib "Giga-tronics") (part "TP-060"))
    )
    (comp (ref "TP57")
      (value ".")
      (footprint "TP-060")
      (fields (field (name "NOLOAD") "N/L") (field (name "APPROVED") "NM"))
      (libsource (lib "Giga-tronics") (part "TP-060"))
    )
    (comp (ref "TP58")
      (value ".")
      (footprint "TP-060")
      (fields (field (name "NOLOAD") "N/L") (field (name "APPROVED") "NM"))
      (libsource (lib "Giga-tronics") (part "TP-060"))
    )
    (comp (ref "TP59")
      (value ".")
      (footprint "TP-060")
      (fields (field (name "NOLOAD") "N/L") (field (name "APPROVED") "NM"))
      (libsource (lib "Giga-tronics") (part "TP-060"))
    )
    (comp (ref "TP60")
      (value ".")
      (footprint "TP-060")
      (fields (field (name "NOLOAD") "N/L") (field (name "APPROVED") "NM"))
      (libsource (lib "Giga-tronics") (part "TP-060"))
    )
    (comp (ref "TP61")
      (value ".")
      (footprint "TP-060")
      (fields (field (name "NOLOAD") "N/L") (field (name "APPROVED") "NM"))
      (libsource (lib "Giga-tronics") (part "TP-060"))
    )
    (comp (ref "TP62")
      (value ".")
      (footprint "TP-060")
      (fields (field (name "NOLOAD") "N/L") (field (name "APPROVED") "NM"))
      (libsource (lib "Giga-tronics") (part "TP-060"))
    )
    (comp (ref "U3")
      (value "QUAD 2 IN OR GATES")
      (footprint "TSSOP-14_ON_SEMI")
      (fields (field (name "APPROVED") "CL"))
      (libsource (lib "Giga-tronics") (part "UTD0-00329"))
    )
    (comp (ref "U37")
      (value "OP-AMP;DUAL:PRECISION;LOW CURRENT;LOW NOISE;WIDE")
      (footprint "SO8_MS-012")
      (fields (field (name "G_PN") "UFD0-08620") (field (name "APPROVED") "CL"))
      (libsource (lib "Giga-tronics") (part "UFD0-08620"))
    )
    (comp (ref "U39")
      (value "OP-AMP;DUAL:PRECISION;LOW CURRENT;LOW NOISE;WIDE")
      (footprint "SO8_MS-012")
      (fields (field (name "G_PN") "UFD0-08620") (field (name "APPROVED") "CL"))
      (libsource (lib "Giga-tronics") (part "UFD0-08620"))
    )
    (comp (ref "U43")
      (value "UTD0-01396")
      (footprint "TSSOP-16_ONSEMI")
      (description "2 TO 4 DECODER/DEMULTIPLEXER;74VHC139 LOGIC;SO-16")
      (fields (field (name "G_PN") "UTD0-01396") (field (name "APPROVED") "CL"))
      (libsource (lib "Giga-tronics") (part "UTD0-01396"))
    )
    (comp (ref "U47")
      (value "74ACT04MTC HEX INVERTER;SMT;TSSOP-14")
      (footprint "TSOP65P640X120-14L")
      (fields (field (name "M_PN") "74ACT04MTC") (field (name "APPROVED") "NM"))
      (libsource (lib "Giga-tronics") (part "UTD4-00046"))
    )
    (comp (ref "U50")
      (value "INVERTER;DUAL;1.65-5.5V SUP;2NS TPD;SC70-6")
      (footprint "SOT-363_419B")
      (fields (field (name "G_PN") "UTD3-00049") (field (name "APPROVED") "CL"))
      (libsource (lib "Giga-tronics") (part "UTD3-00049"))
    )
  )
  (nets
    (net (code "1") (name "+5V_SW") (class "Default")
      (node (ref "C112") (pin "1") (pintype "passive"))
      (node (ref "C654") (pin "1") (pintype "passive"))
      (node (ref "FT24") (pin "1") (pinfunction "1_1") (pintype "passive"))
      (node (ref "R167") (pin "2") (pintype "passive"))
      (node (ref "R168") (pin "2") (pintype "passive"))
      (node (ref "R169") (pin "2") (pintype "passive"))
      (node (ref "R170") (pin "2") (pintype "passive"))
      (node (ref "R192") (pin "2") (pintype "passive"))
      (node (ref "R193") (pin "2") (pintype "passive"))
      (node (ref "R202") (pin "2") (pintype "passive"))
      (node (ref "R203") (pin "2") (pintype "passive"))
      (node (ref "R204") (pin "2") (pintype "passive"))
      (node (ref "R205") (pin "2") (pintype "passive"))
      (node (ref "R206") (pin "2") (pintype "passive"))
      (node (ref "R207") (pin "2") (pintype "passive"))
      (node (ref "R221") (pin "2") (pintype "passive"))
      (node (ref "R224") (pin "2") (pintype "passive"))
      (node (ref "R251") (pin "2") (pintype "passive"))
      (node (ref "R268") (pin "2") (pintype "passive"))
      (node (ref "SW15") (pin "12") (pinfunction "VL_12") (pintype "passive"))
      (node (ref "SW15") (pin "13") (pinfunction "V+_13") (pintype "passive"))
      (node (ref "SW16") (pin "12") (pinfunction "VL_12") (pintype "passive"))
      (node (ref "SW16") (pin "13") (pinfunction "V+_13") (pintype "passive"))
      (node (ref "SW17") (pin "12") (pinfunction "VL_12") (pintype "passive"))
      (node (ref "SW17") (pin "13") (pinfunction "V+_13") (pintype "passive"))
      (node (ref "SW18") (pin "12") (pinfunction "VL_12") (pintype "passive"))
      (node (ref "SW18") (pin "13") (pinfunction "V+_13") (pintype "passive"))
      (node (ref "SW19") (pin "12") (pinfunction "VL_12") (pintype "passive"))
      (node (ref "SW19") (pin "13") (pinfunction "V+_13") (pintype "passive"))
      (node (ref "SW20") (pin "12") (pinfunction "VL_12") (pintype "passive"))
      (node (ref "SW20") (pin "13") (pinfunction "V+_13") (pintype "passive"))
      (node (ref "SW21") (pin "12") (pinfunction "VL_12") (pintype "passive"))
      (node (ref "SW21") (pin "13") (pinfunction "V+_13") (pintype "passive"))
      (node (ref "SW23") (pin "12") (pinfunction "VL_12") (pintype "passive"))
      (node (ref "SW23") (pin "13") (pinfunction "V+_13") (pintype "passive"))
      (node (ref "U3") (pin "14") (pinfunction "Vcc_14") (pintype "passive"))
      (node (ref "U43") (pin "16") (pinfunction "VCC_16") (pintype "passive"))
      (node (ref "U47") (pin "14") (pinfunction "VCC_14") (pintype "passive"))
      (node (ref "U50") (pin "5") (pinfunction "V+_5") (pintype "passive"))
    )
    (net (code "2") (name "+5V_alc") (class "Default")
      (node (ref "C608") (pin "1") (pintype "passive"))
      (node (ref "C609") (pin "1") (pintype "passive"))
      (node (ref "C610") (pin "1") (pintype "passive"))
      (node (ref "C611") (pin "1") (pintype "passive"))
      (node (ref "FT16") (pin "1") (pinfunction "1_1") (pintype "passive"))
      (node (ref "R92") (pin "1") (pintype "passive"))
      (node (ref "U37") (pin "8") (pinfunction "V+_8") (pintype "passive"))
      (node (ref "U39") (pin "8") (pinfunction "V+_8") (pintype "passive"))
    )
    (net (code "3") (name "-10V_alc") (class "Default")
      (node (ref "C612") (pin "1") (pintype "passive"))
      (node (ref "C613") (pin "1") (pintype "passive"))
      (node (ref "C614") (pin "1") (pintype "passive"))
      (node (ref "C615") (pin "1") (pintype "passive"))
      (node (ref "FT10") (pin "1") (pinfunction "1_1") (pintype "passive"))
      (node (ref "U37") (pin "4") (pinfunction "V-_4") (pintype "passive"))
      (node (ref "U39") (pin "4") (pinfunction "V-_4") (pintype "passive"))
    )
    (net (code "4") (name "-12V_SW") (class "Default")
      (node (ref "R164") (pin "2") (pintype "passive"))
      (node (ref "R165") (pin "2") (pintype "passive"))
      (node (ref "R166") (pin "2") (pintype "passive"))
      (node (ref "R194") (pin "2") (pintype "passive"))
      (node (ref "R195") (pin "2") (pintype "passive"))
      (node (ref "R197") (pin "2") (pintype "passive"))
      (node (ref "R198") (pin "2") (pintype "passive"))
      (node (ref "R200") (pin "2") (pintype "passive"))
      (node (ref "R201") (pin "2") (pintype "passive"))
      (node (ref "R208") (pin "2") (pintype "passive"))
      (node (ref "R212") (pin "2") (pintype "passive"))
      (node (ref "R216") (pin "2") (pintype "passive"))
      (node (ref "R220") (pin "2") (pintype "passive"))
      (node (ref "R233") (pin "2") (pintype "passive"))
      (node (ref "R250") (pin "2") (pintype "passive"))
      (node (ref "R348") (pin "2") (pintype "passive"))
      (node (ref "SW15") (pin "4") (pinfunction "VL_4") (pintype "passive"))
      (node (ref "SW16") (pin "4") (pinfunction "VL_4") (pintype "passive"))
      (node (ref "SW17") (pin "4") (pinfunction "VL_4") (pintype "passive"))
      (node (ref "SW18") (pin "4") (pinfunction "VL_4") (pintype "passive"))
      (node (ref "SW19") (pin "4") (pinfunction "VL_4") (pintype "passive"))
      (node (ref "SW20") (pin "4") (pinfunction "VL_4") (pintype "passive"))
      (node (ref "SW21") (pin "4") (pinfunction "VL_4") (pintype "passive"))
      (node (ref "SW23") (pin "4") (pinfunction "VL_4") (pintype "passive"))
    )
    (net (code "5") (name "/8_GHz_LPF") (class "Default")
      (node (ref "R238") (pin "2") (pintype "passive"))
      (node (ref "SW17") (pin "1") (pinfunction "IN1_1") (pintype "passive"))
      (node (ref "SW17") (pin "16") (pinfunction "S1_16") (pintype "passive"))
      (node (ref "SW17") (pin "8") (pinfunction "IN4_8") (pintype "passive"))
      (node (ref "SW17") (pin "9") (pinfunction "IN3_9") (pintype "passive"))
    )
    (net (code "6") (name "/20_GHz_LPF_A1-A2") (class "Default")
      (node (ref "R235") (pin "2") (pintype "passive"))
      (node (ref "SW20") (pin "1") (pinfunction "IN1_1") (pintype "passive"))
      (node (ref "SW20") (pin "16") (pinfunction "S1_16") (pintype "passive"))
      (node (ref "SW20") (pin "8") (pinfunction "IN4_8") (pintype "passive"))
      (node (ref "SW20") (pin "9") (pinfunction "IN3_9") (pintype "passive"))
    )
    (net (code "7") (name "/A1-A2_FILTER_A") (class "Default")
      (node (ref "U43") (pin "14") (pinfunction "A0b_14") (pintype "passive"))
      (node (ref "U43") (pin "2") (pinfunction "A0a_2") (pintype "passive"))
    )
    (net (code "8") (name "/A1-A2_FILTER_B") (class "Default")
      (node (ref "U43") (pin "13") (pinfunction "A1b_13") (pintype "passive"))
      (node (ref "U43") (pin "3") (pinfunction "A1a_3") (pintype "passive"))
    )
    (net (code "9") (name "/A1-A2_FILTER_C") (class "Default")
      (node (ref "SW18") (pin "1") (pinfunction "IN1_1") (pintype "passive"))
      (node (ref "SW18") (pin "16") (pinfunction "S1_16") (pintype "passive"))
      (node (ref "SW18") (pin "8") (pinfunction "IN4_8") (pintype "passive"))
      (node (ref "SW18") (pin "9") (pinfunction "IN3_9") (pintype "passive"))
      (node (ref "U43") (pin "15") (pinfunction "~{Eb}_15") (pintype "passive"))
      (node (ref "U50") (pin "3") (pinfunction "IN_3") (pintype "passive"))
    )
    (net (code "10") (name "/A1-A2_VVA_series") (class "Default")
      (node (ref "A1") (pin "T86") (pinfunction "T86_T86") (pintype "passive"))
      (node (ref "A1") (pin "T88") (pinfunction "T88_T88") (pintype "passive"))
      (node (ref "R70") (pin "2") (pintype "passive"))
      (node (ref "R72") (pin "2") (pintype "passive"))
      (node (ref "T86") (pin "1") (pintype "passive"))
      (node (ref "T88") (pin "1") (pintype "passive"))
    )
    (net (code "11") (name "/A1-A2_VVA_shunt") (class "Default")
      (node (ref "A1") (pin "T85") (pinfunction "T85_T85") (pintype "passive"))
      (node (ref "A1") (pin "T87") (pinfunction "T87_T87") (pintype "passive"))
      (node (ref "R78") (pin "2") (pintype "passive"))
      (node (ref "R81") (pin "2") (pintype "passive"))
      (node (ref "T85") (pin "1") (pintype "passive"))
      (node (ref "T87") (pin "1") (pintype "passive"))
    )
    (net (code "12") (name "/ALC_VAR_ATTN_HIBAND_IOUT_N") (class "Default")
      (node (ref "R82") (pin "1") (pintype "passive"))
    )
    (net (code "13") (name "/ALC_VAR_ATTN_HIBAND_IOUT_P") (class "Default")
      (node (ref "R75") (pin "1") (pintype "passive"))
    )
    (net (code "14") (name "/DC_BYPASS") (class "Default")
      (node (ref "R387") (pin "1") (pintype "passive"))
      (node (ref "U3") (pin "6") (pinfunction "O1_6") (pintype "passive"))
    )
    (net (code "15") (name "/DC_HIGH_BAND") (class "Default")
      (node (ref "R388") (pin "1") (pintype "passive"))
      (node (ref "U3") (pin "8") (pinfunction "O3_8") (pintype "passive"))
    )
    (net (code "16") (name "/DC_LOW_BAND") (class "Default")
      (node (ref "R386") (pin "1") (pintype "passive"))
      (node (ref "U3") (pin "3") (pinfunction "O0_3") (pintype "passive"))
    )
    (net (code "17") (name "/RF_OUT") (class "Default")
      (node (ref "A1") (pin "MH_RF_OUT") (pinfunction "RF_OUT_MH_RF_OUT") (pintype "passive+no_connect"))
    )
    (net (code "18") (name "/SW15-1") (class "Default")
      (node (ref "R405") (pin "2") (pintype "passive"))
      (node (ref "R408") (pin "2") (pintype "passive"))
      (node (ref "SW15") (pin "1") (pinfunction "IN1_1") (pintype "passive"))
      (node (ref "SW15") (pin "16") (pinfunction "S1_16") (pintype "passive"))
      (node (ref "SW15") (pin "8") (pinfunction "IN4_8") (pintype "passive"))
      (node (ref "SW15") (pin "9") (pinfunction "IN3_9") (pintype "passive"))
    )
    (net (code "19") (name "/SW16-1") (class "Default")
      (node (ref "R387") (pin "2") (pintype "passive"))
      (node (ref "R393") (pin "2") (pintype "passive"))
      (node (ref "SW16") (pin "1") (pinfunction "IN1_1") (pintype "passive"))
      (node (ref "SW16") (pin "16") (pinfunction "S1_16") (pintype "passive"))
      (node (ref "SW16") (pin "8") (pinfunction "IN4_8") (pintype "passive"))
      (node (ref "SW16") (pin "9") (pinfunction "IN3_9") (pintype "passive"))
    )
    (net (code "20") (name "/SW19-1") (class "Default")
      (node (ref "R395") (pin "2") (pintype "passive"))
      (node (ref "R404") (pin "2") (pintype "passive"))
      (node (ref "SW19") (pin "1") (pinfunction "IN1_1") (pintype "passive"))
      (node (ref "SW19") (pin "16") (pinfunction "S1_16") (pintype "passive"))
      (node (ref "SW19") (pin "8") (pinfunction "IN4_8") (pintype "passive"))
      (node (ref "SW19") (pin "9") (pinfunction "IN3_9") (pintype "passive"))
    )
    (net (code "21") (name "/SW21-1") (class "Default")
      (node (ref "R388") (pin "2") (pintype "passive"))
      (node (ref "R394") (pin "2") (pintype "passive"))
      (node (ref "SW21") (pin "1") (pinfunction "IN1_1") (pintype "passive"))
      (node (ref "SW21") (pin "16") (pinfunction "S1_16") (pintype "passive"))
    )
    (net (code "22") (name "/SW23-1") (class "Default")
      (node (ref "R385") (pin "2") (pintype "passive"))
      (node (ref "R386") (pin "2") (pintype "passive"))
      (node (ref "SW21") (pin "8") (pinfunction "IN4_8") (pintype "passive"))
      (node (ref "SW21") (pin "9") (pinfunction "IN3_9") (pintype "passive"))
      (node (ref "SW23") (pin "1") (pinfunction "IN1_1") (pintype "passive"))
      (node (ref "SW23") (pin "16") (pinfunction "S1_16") (pintype "passive"))
      (node (ref "SW23") (pin "8") (pinfunction "IN4_8") (pintype "passive"))
      (node (ref "SW23") (pin "9") (pinfunction "IN3_9") (pintype "passive"))
    )
    (net (code "23") (name "/T51") (class "Default")
      (node (ref "SW23") (pin "15") (pinfunction "D2_15") (pintype "passive"))
      (node (ref "SW23") (pin "2") (pinfunction "D1_2") (pintype "passive"))
      (node (ref "T51") (pin "1") (pintype "passive"))
      (node (ref "TP61") (pin "1") (pinfunction "1_1") (pintype "passive"))
    )
    (net (code "24") (name "/T52") (class "Default")
      (node (ref "SW21") (pin "15") (pinfunction "D2_15") (pintype "passive"))
      (node (ref "SW21") (pin "2") (pinfunction "D1_2") (pintype "passive"))
      (node (ref "T52") (pin "1") (pintype "passive"))
      (node (ref "TP60") (pin "1") (pinfunction "1_1") (pintype "passive"))
    )
    (net (code "25") (name "/T89") (class "Default")
      (node (ref "A1") (pin "T89") (pinfunction "T89_T89") (pintype "passive"))
    )
    (net (code "26") (name "/T90") (class "Default")
      (node (ref "A1") (pin "T90") (pinfunction "T90_T90") (pintype "passive"))
      (node (ref "SW21") (pin "10") (pinfunction "D3_10") (pintype "passive"))
      (node (ref "SW21") (pin "7") (pinfunction "D4_7") (pintype "passive"))
      (node (ref "SW23") (pin "10") (pinfunction "D3_10") (pintype "passive"))
      (node (ref "SW23") (pin "7") (pinfunction "D4_7") (pintype "passive"))
      (node (ref "T90") (pin "1") (pintype "passive"))
      (node (ref "TP62") (pin "1") (pinfunction "1_1") (pintype "passive"))
    )
    (net (code "27") (name "/T91") (class "Default")
      (node (ref "A1") (pin "T91") (pinfunction "T91_T91") (pintype "passive"))
      (node (ref "SW18") (pin "15") (pinfunction "D2_15") (pintype "passive"))
      (node (ref "SW18") (pin "2") (pinfunction "D1_2") (pintype "passive"))
      (node (ref "T91") (pin "1") (pintype "passive"))
      (node (ref "TP54") (pin "1") (pinfunction "1_1") (pintype "passive"))
    )
    (net (code "28") (name "/T92") (class "Default")
      (node (ref "A1") (pin "T92") (pinfunction "T92_T92") (pintype "passive"))
      (node (ref "SW15") (pin "10") (pinfunction "D3_10") (pintype "passive"))
      (node (ref "SW15") (pin "15") (pinfunction "D2_15") (pintype "passive"))
      (node (ref "SW15") (pin "2") (pinfunction "D1_2") (pintype "passive"))
      (node (ref "SW15") (pin "7") (pinfunction "D4_7") (pintype "passive"))
      (node (ref "T92") (pin "1") (pintype "passive"))
      (node (ref "TP51") (pin "1") (pinfunction "1_1") (pintype "passive"))
    )
    (net (code "29") (name "/T93") (class "Default")
      (node (ref "A1") (pin "T93") (pinfunction "T93_T93") (pintype "passive"))
      (node (ref "SW17") (pin "10") (pinfunction "D3_10") (pintype "passive"))
      (node (ref "SW17") (pin "15") (pinfunction "D2_15") (pintype "passive"))
      (node (ref "SW17") (pin "2") (pinfunction "D1_2") (pintype "passive"))
      (node (ref "SW17") (pin "7") (pinfunction "D4_7") (pintype "passive"))
      (node (ref "T93") (pin "1") (pintype "passive"))
      (node (ref "TP53") (pin "1") (pinfunction "1_1") (pintype "passive"))
    )
    (net (code "30") (name "/T94") (class "Default")
      (node (ref "A1") (pin "T94") (pinfunction "T94_T94") (pintype "passive"))
      (node (ref "SW16") (pin "10") (pinfunction "D3_10") (pintype "passive"))
      (node (ref "SW16") (pin "15") (pinfunction "D2_15") (pintype "passive"))
      (node (ref "SW16") (pin "2") (pinfunction "D1_2") (pintype "passive"))
      (node (ref "SW16") (pin "7") (pinfunction "D4_7") (pintype "passive"))
      (node (ref "T94") (pin "1") (pintype "passive"))
      (node (ref "TP52") (pin "1") (pinfunction "1_1") (pintype "passive"))
    )
    (net (code "31") (name "/T95") (class "Default")
      (node (ref "A1") (pin "T95") (pinfunction "T95_T95") (pintype "passive"))
      (node (ref "SW20") (pin "15") (pinfunction "D2_15") (pintype "passive"))
      (node (ref "SW20") (pin "2") (pinfunction "D1_2") (pintype "passive"))
      (node (ref "T95") (pin "1") (pintype "passive"))
      (node (ref "TP56") (pin "1") (pinfunction "1_1") (pintype "passive"))
    )
    (net (code "32") (name "/T96") (class "Default")
      (node (ref "A1") (pin "T96") (pinfunction "T96_T96") (pintype "passive"))
      (node (ref "SW19") (pin "15") (pinfunction "D2_15") (pintype "passive"))
      (node (ref "SW19") (pin "2") (pinfunction "D1_2") (pintype "passive"))
      (node (ref "T96") (pin "1") (pintype "passive"))
      (node (ref "TP55") (pin "1") (pinfunction "1_1") (pintype "passive"))
    )
    (net (code "33") (name "/T97") (class "Default")
      (node (ref "A1") (pin "T97") (pinfunction "T97_T97") (pintype "passive"))
      (node (ref "SW18") (pin "10") (pinfunction "D3_10") (pintype "passive"))
      (node (ref "SW18") (pin "7") (pinfunction "D4_7") (pintype "passive"))
      (node (ref "T97") (pin "1") (pintype "passive"))
      (node (ref "TP57") (pin "1") (pinfunction "1_1") (pintype "passive"))
    )
    (net (code "34") (name "/T98") (class "Default")
      (node (ref "A1") (pin "T98") (pinfunction "T98_T98") (pintype "passive"))
      (node (ref "SW20") (pin "10") (pinfunction "D3_10") (pintype "passive"))
      (node (ref "SW20") (pin "7") (pinfunction "D4_7") (pintype "passive"))
      (node (ref "T98") (pin "1") (pintype "passive"))
      (node (ref "TP59") (pin "1") (pinfunction "1_1") (pintype "passive"))
    )
    (net (code "35") (name "/T99") (class "Default")
      (node (ref "A1") (pin "T99") (pinfunction "T99_T99") (pintype "passive"))
      (node (ref "SW19") (pin "10") (pinfunction "D3_10") (pintype "passive"))
      (node (ref "SW19") (pin "7") (pinfunction "D4_7") (pintype "passive"))
      (node (ref "T99") (pin "1") (pintype "passive"))
      (node (ref "TP58") (pin "1") (pinfunction "1_1") (pintype "passive"))
    )
    (net (code "36") (name "/T100") (class "Default")
      (node (ref "A1") (pin "T100") (pinfunction "T100_T100") (pintype "passive"))
    )
    (net (code "37") (name "/T101_102") (class "Default")
      (node (ref "A1") (pin "T101") (pinfunction "T101_T101") (pintype "passive"))
      (node (ref "A1") (pin "T102") (pinfunction "T102_T102") (pintype "passive"))
    )
    (net (code "38") (name "/T103") (class "Default")
      (node (ref "A1") (pin "T103") (pinfunction "T103_T103") (pintype "passive"))
    )
    (net (code "39") (name "/UC_HIGH_BAND") (class "Default")
      (node (ref "R107") (pin "2") (pintype "passive"))
      (node (ref "R394") (pin "1") (pintype "passive"))
    )
    (net (code "40") (name "/Y0a") (class "Default")
      (node (ref "R236") (pin "2") (pintype "passive"))
      (node (ref "R408") (pin "1") (pintype "passive"))
      (node (ref "U3") (pin "5") (pinfunction "B1_5") (pintype "passive"))
      (node (ref "U3") (pin "9") (pinfunction "B3_9") (pintype "passive"))
    )
    (net (code "41") (name "/Y0b") (class "Default")
      (node (ref "R245") (pin "2") (pintype "passive"))
      (node (ref "R385") (pin "1") (pintype "passive"))
      (node (ref "R395") (pin "1") (pintype "passive"))
      (node (ref "U3") (pin "1") (pinfunction "A0_1") (pintype "passive"))
    )
    (net (code "42") (name "/Y1a") (class "Default")
      (node (ref "R237") (pin "2") (pintype "passive"))
      (node (ref "R393") (pin "1") (pintype "passive"))
      (node (ref "R405") (pin "1") (pintype "passive"))
      (node (ref "U3") (pin "10") (pinfunction "A3_10") (pintype "passive"))
    )
    (net (code "43") (name "/Y1b") (class "Default")
      (node (ref "R234") (pin "2") (pintype "passive"))
      (node (ref "R404") (pin "1") (pintype "passive"))
      (node (ref "U3") (pin "2") (pinfunction "B0_2") (pintype "passive"))
      (node (ref "U3") (pin "4") (pinfunction "A1_4") (pintype "passive"))
    )
    (net (code "44") (name "GND") (class "Default")
      (node (ref "A1") (pin "A1-A2_shield") (pinfunction "shield_A1-A2_shield") (pintype "passive"))
      (node (ref "A1") (pin "MH1") (pinfunction "MH1_MH1") (pintype "passive"))
      (node (ref "C112") (pin "2") (pintype "passive"))
      (node (ref "C608") (pin "2") (pintype "passive"))
      (node (ref "C609") (pin "2") (pintype "passive"))
      (node (ref "C610") (pin "2") (pintype "passive"))
      (node (ref "C611") (pin "2") (pintype "passive"))
      (node (ref "C612") (pin "2") (pintype "passive"))
      (node (ref "C613") (pin "2") (pintype "passive"))
      (node (ref "C614") (pin "2") (pintype "passive"))
      (node (ref "C615") (pin "2") (pintype "passive"))
      (node (ref "C654") (pin "2") (pintype "passive"))
      (node (ref "CR2") (pin "2") (pinfunction "A_2") (pintype "passive"))
      (node (ref "R67") (pin "1") (pintype "passive"))
      (node (ref "R72") (pin "1") (pintype "passive"))
      (node (ref "R81") (pin "1") (pintype "passive"))
      (node (ref "R84") (pin "2") (pintype "passive"))
      (node (ref "R89") (pin "1") (pintype "passive"))
      (node (ref "SW15") (pin "5") (pinfunction "IN2_5") (pintype "passive"))
      (node (ref "SW16") (pin "5") (pinfunction "IN2_5") (pintype "passive"))
      (node (ref "SW17") (pin "5") (pinfunction "IN2_5") (pintype "passive"))
      (node (ref "SW18") (pin "5") (pinfunction "IN2_5") (pintype "passive"))
      (node (ref "SW19") (pin "5") (pinfunction "IN2_5") (pintype "passive"))
      (node (ref "SW20") (pin "5") (pinfunction "IN2_5") (pintype "passive"))
      (node (ref "SW21") (pin "5") (pinfunction "IN2_5") (pintype "passive"))
      (node (ref "SW23") (pin "5") (pinfunction "IN2_5") (pintype "passive"))
      (node (ref "U3") (pin "12") (pinfunction "B2_12") (pintype "passive"))
      (node (ref "U3") (pin "13") (pinfunction "A2_13") (pintype "passive"))
      (node (ref "U3") (pin "7") (pinfunction "GND_7") (pintype "passive"))
      (node (ref "U37") (pin "3") (pinfunction "+IN_3") (pintype "passive"))
      (node (ref "U43") (pin "8") (pinfunction "GND_8") (pintype "passive"))
      (node (ref "U47") (pin "7") (pinfunction "GND_7") (pintype "passive"))
      (node (ref "U50") (pin "1") (pinfunction "IN_1") (pintype "passive"))
      (node (ref "U50") (pin "2") (pinfunction "V-_2") (pintype "passive"))
    )
    (net (code "45") (name "Net-(CR2-C)") (class "Default")
      (node (ref "CR2") (pin "1") (pinfunction "C_1") (pintype "passive"))
      (node (ref "R92") (pin "2") (pintype "passive"))
      (node (ref "U39") (pin "5") (pinfunction "+IN_5") (pintype "passive"))
    )
    (net (code "46") (name "Net-(R164-Pad1)") (class "Default")
      (node (ref "R164") (pin "1") (pintype "passive"))
      (node (ref "SW15") (pin "3") (pinfunction "S1_3") (pintype "passive"))
    )
    (net (code "47") (name "Net-(R165-Pad1)") (class "Default")
      (node (ref "R165") (pin "1") (pintype "passive"))
      (node (ref "SW16") (pin "3") (pinfunction "S1_3") (pintype "passive"))
    )
    (net (code "48") (name "Net-(R166-Pad1)") (class "Default")
      (node (ref "R166") (pin "1") (pintype "passive"))
      (node (ref "SW17") (pin "3") (pinfunction "S1_3") (pintype "passive"))
    )
    (net (code "49") (name "Net-(R198-Pad1)") (class "Default")
      (node (ref "R198") (pin "1") (pintype "passive"))
      (node (ref "SW18") (pin "3") (pinfunction "S1_3") (pintype "passive"))
    )
    (net (code "50") (name "Net-(R200-Pad1)") (class "Default")
      (node (ref "R200") (pin "1") (pintype "passive"))
      (node (ref "SW19") (pin "3") (pinfunction "S1_3") (pintype "passive"))
    )
    (net (code "51") (name "Net-(R201-Pad1)") (class "Default")
      (node (ref "R201") (pin "1") (pintype "passive"))
      (node (ref "SW20") (pin "3") (pinfunction "S1_3") (pintype "passive"))
    )
    (net (code "52") (name "Net-(R220-Pad1)") (class "Default")
      (node (ref "R220") (pin "1") (pintype "passive"))
      (node (ref "SW21") (pin "3") (pinfunction "S1_3") (pintype "passive"))
    )
    (net (code "53") (name "Net-(R234-Pad1)") (class "Default")
      (node (ref "R234") (pin "1") (pintype "passive"))
      (node (ref "U47") (pin "4") (pintype "passive"))
    )
    (net (code "54") (name "Net-(R235-Pad1)") (class "Default")
      (node (ref "R235") (pin "1") (pintype "passive"))
      (node (ref "U47") (pin "6") (pintype "passive"))
    )
    (net (code "55") (name "Net-(R236-Pad1)") (class "Default")
      (node (ref "R236") (pin "1") (pintype "passive"))
      (node (ref "U47") (pin "12") (pintype "passive"))
    )
    (net (code "56") (name "Net-(R237-Pad1)") (class "Default")
      (node (ref "R237") (pin "1") (pintype "passive"))
      (node (ref "U47") (pin "10") (pintype "passive"))
    )
    (net (code "57") (name "Net-(R238-Pad1)") (class "Default")
      (node (ref "R238") (pin "1") (pintype "passive"))
      (node (ref "U47") (pin "8") (pintype "passive"))
    )
    (net (code "58") (name "Net-(R245-Pad1)") (class "Default")
      (node (ref "R245") (pin "1") (pintype "passive"))
      (node (ref "U47") (pin "2") (pintype "passive"))
    )
    (net (code "59") (name "Net-(R250-Pad1)") (class "Default")
      (node (ref "R250") (pin "1") (pintype "passive"))
      (node (ref "SW23") (pin "3") (pinfunction "S1_3") (pintype "passive"))
    )
    (net (code "60") (name "Net-(SW15-S2)") (class "Default")
      (node (ref "R167") (pin "1") (pintype "passive"))
      (node (ref "SW15") (pin "14") (pinfunction "S2_14") (pintype "passive"))
    )
    (net (code "61") (name "Net-(SW15-S3)") (class "Default")
      (node (ref "R170") (pin "1") (pintype "passive"))
      (node (ref "SW15") (pin "11") (pinfunction "S3_11") (pintype "passive"))
    )
    (net (code "62") (name "Net-(SW15-S4)") (class "Default")
      (node (ref "R194") (pin "1") (pintype "passive"))
      (node (ref "SW15") (pin "6") (pinfunction "S4_6") (pintype "passive"))
    )
    (net (code "63") (name "Net-(SW16-S2)") (class "Default")
      (node (ref "R168") (pin "1") (pintype "passive"))
      (node (ref "SW16") (pin "14") (pinfunction "S2_14") (pintype "passive"))
    )
    (net (code "64") (name "Net-(SW16-S3)") (class "Default")
      (node (ref "R192") (pin "1") (pintype "passive"))
      (node (ref "SW16") (pin "11") (pinfunction "S3_11") (pintype "passive"))
    )
    (net (code "65") (name "Net-(SW16-S4)") (class "Default")
      (node (ref "R195") (pin "1") (pintype "passive"))
      (node (ref "SW16") (pin "6") (pinfunction "S4_6") (pintype "passive"))
    )
    (net (code "66") (name "Net-(SW17-S2)") (class "Default")
      (node (ref "R169") (pin "1") (pintype "passive"))
      (node (ref "SW17") (pin "14") (pinfunction "S2_14") (pintype "passive"))
    )
    (net (code "67") (name "Net-(SW17-S3)") (class "Default")
      (node (ref "R193") (pin "1") (pintype "passive"))
      (node (ref "SW17") (pin "11") (pinfunction "S3_11") (pintype "passive"))
    )
    (net (code "68") (name "Net-(SW17-S4)") (class "Default")
      (node (ref "R197") (pin "1") (pintype "passive"))
      (node (ref "SW17") (pin "6") (pinfunction "S4_6") (pintype "passive"))
    )
    (net (code "69") (name "Net-(SW18-S2)") (class "Default")
      (node (ref "R202") (pin "1") (pintype "passive"))
      (node (ref "SW18") (pin "14") (pinfunction "S2_14") (pintype "passive"))
    )
    (net (code "70") (name "Net-(SW18-S3)") (class "Default")
      (node (ref "R205") (pin "1") (pintype "passive"))
      (node (ref "SW18") (pin "11") (pinfunction "S3_11") (pintype "passive"))
    )
    (net (code "71") (name "Net-(SW18-S4)") (class "Default")
      (node (ref "R208") (pin "1") (pintype "passive"))
      (node (ref "SW18") (pin "6") (pinfunction "S4_6") (pintype "passive"))
    )
    (net (code "72") (name "Net-(SW19-S2)") (class "Default")
      (node (ref "R203") (pin "1") (pintype "passive"))
      (node (ref "SW19") (pin "14") (pinfunction "S2_14") (pintype "passive"))
    )
    (net (code "73") (name "Net-(SW19-S3)") (class "Default")
      (node (ref "R206") (pin "1") (pintype "passive"))
      (node (ref "SW19") (pin "11") (pinfunction "S3_11") (pintype "passive"))
    )
    (net (code "74") (name "Net-(SW19-S4)") (class "Default")
      (node (ref "R212") (pin "1") (pintype "passive"))
      (node (ref "SW19") (pin "6") (pinfunction "S4_6") (pintype "passive"))
    )
    (net (code "75") (name "Net-(SW20-S2)") (class "Default")
      (node (ref "R204") (pin "1") (pintype "passive"))
      (node (ref "SW20") (pin "14") (pinfunction "S2_14") (pintype "passive"))
    )
    (net (code "76") (name "Net-(SW20-S3)") (class "Default")
      (node (ref "R207") (pin "1") (pintype "passive"))
      (node (ref "SW20") (pin "11") (pinfunction "S3_11") (pintype "passive"))
    )
    (net (code "77") (name "Net-(SW20-S4)") (class "Default")
      (node (ref "R216") (pin "1") (pintype "passive"))
      (node (ref "SW20") (pin "6") (pinfunction "S4_6") (pintype "passive"))
    )
    (net (code "78") (name "Net-(SW21-S2)") (class "Default")
      (node (ref "R221") (pin "1") (pintype "passive"))
      (node (ref "SW21") (pin "14") (pinfunction "S2_14") (pintype "passive"))
    )
    (net (code "79") (name "Net-(SW21-S3)") (class "Default")
      (node (ref "R224") (pin "1") (pintype "passive"))
      (node (ref "SW21") (pin "11") (pinfunction "S3_11") (pintype "passive"))
    )
    (net (code "80") (name "Net-(SW21-S4)") (class "Default")
      (node (ref "R233") (pin "1") (pintype "passive"))
      (node (ref "SW21") (pin "6") (pinfunction "S4_6") (pintype "passive"))
    )
    (net (code "81") (name "Net-(SW23-S2)") (class "Default")
      (node (ref "R251") (pin "1") (pintype "passive"))
      (node (ref "SW23") (pin "14") (pinfunction "S2_14") (pintype "passive"))
    )
    (net (code "82") (name "Net-(SW23-S3)") (class "Default")
      (node (ref "R268") (pin "1") (pintype "passive"))
      (node (ref "SW23") (pin "11") (pinfunction "S3_11") (pintype "passive"))
    )
    (net (code "83") (name "Net-(SW23-S4)") (class "Default")
      (node (ref "R348") (pin "1") (pintype "passive"))
      (node (ref "SW23") (pin "6") (pinfunction "S4_6") (pintype "passive"))
    )
    (net (code "84") (name "Net-(U37A--IN)") (class "Default")
      (node (ref "C617") (pin "1") (pintype "passive"))
      (node (ref "R79") (pin "2") (pintype "passive"))
      (node (ref "R85") (pin "2") (pintype "passive"))
      (node (ref "R86") (pin "1") (pintype "passive"))
      (node (ref "U37") (pin "2") (pinfunction "-IN_2") (pintype "passive"))
    )
    (net (code "85") (name "Net-(U37A-OUT)") (class "Default")
      (node (ref "C617") (pin "2") (pintype "passive"))
      (node (ref "R78") (pin "1") (pintype "passive"))
      (node (ref "R86") (pin "2") (pintype "passive"))
      (node (ref "U37") (pin "1") (pinfunction "OUT_1") (pintype "passive"))
    )
    (net (code "86") (name "Net-(U37B-+IN)") (class "Default")
      (node (ref "R71") (pin "2") (pintype "passive"))
      (node (ref "U37") (pin "5") (pinfunction "+IN_5") (pintype "passive"))
    )
    (net (code "87") (name "Net-(U37B--IN)") (class "Default")
      (node (ref "C606") (pin "1") (pintype "passive"))
      (node (ref "R67") (pin "2") (pintype "passive"))
      (node (ref "R68") (pin "1") (pintype "passive"))
      (node (ref "U37") (pin "6") (pinfunction "-IN_6") (pintype "passive"))
    )
    (net (code "88") (name "Net-(U37B-OUT)") (class "Default")
      (node (ref "C606") (pin "2") (pintype "passive"))
      (node (ref "R68") (pin "2") (pintype "passive"))
      (node (ref "R70") (pin "1") (pintype "passive"))
      (node (ref "U37") (pin "7") (pinfunction "OUT_7") (pintype "passive"))
    )
    (net (code "89") (name "Net-(U39A-+IN)") (class "Default")
      (node (ref "R82") (pin "2") (pintype "passive"))
      (node (ref "R84") (pin "1") (pintype "passive"))
      (node (ref "U39") (pin "3") (pinfunction "+IN_3") (pintype "passive"))
    )
    (net (code "90") (name "Net-(U39A--IN)") (class "Default")
      (node (ref "C607") (pin "1") (pintype "passive"))
      (node (ref "R73") (pin "1") (pintype "passive"))
      (node (ref "R75") (pin "2") (pintype "passive"))
      (node (ref "U39") (pin "2") (pinfunction "-IN_2") (pintype "passive"))
    )
    (net (code "91") (name "Net-(U39A-OUT)") (class "Default")
      (node (ref "C607") (pin "2") (pintype "passive"))
      (node (ref "R71") (pin "1") (pintype "passive"))
      (node (ref "R73") (pin "2") (pintype "passive"))
      (node (ref "R79") (pin "1") (pintype "passive"))
      (node (ref "U39") (pin "1") (pinfunction "OUT_1") (pintype "passive"))
    )
    (net (code "92") (name "Net-(U39B--IN)") (class "Default")
      (node (ref "C616") (pin "1") (pintype "passive"))
      (node (ref "R89") (pin "2") (pintype "passive"))
      (node (ref "R90") (pin "1") (pintype "passive"))
      (node (ref "U39") (pin "6") (pinfunction "-IN_6") (pintype "passive"))
    )
    (net (code "93") (name "Net-(U39B-OUT)") (class "Default")
      (node (ref "C616") (pin "2") (pintype "passive"))
      (node (ref "R85") (pin "1") (pintype "passive"))
      (node (ref "R90") (pin "2") (pintype "passive"))
      (node (ref "U39") (pin "7") (pinfunction "OUT_7") (pintype "passive"))
    )
    (net (code "94") (name "Net-(U43-~{Ea})") (class "Default")
      (node (ref "U43") (pin "1") (pinfunction "~{Ea}_1") (pintype "passive"))
      (node (ref "U50") (pin "4") (pinfunction "OUT_4") (pintype "passive"))
    )
    (net (code "95") (name "Net-(U43-~{Y0a})") (class "Default")
      (node (ref "U43") (pin "4") (pinfunction "~{Y0a}_4") (pintype "passive"))
      (node (ref "U47") (pin "13") (pintype "passive"))
    )
    (net (code "96") (name "Net-(U43-~{Y0b})") (class "Default")
      (node (ref "R107") (pin "1") (pintype "passive"))
      (node (ref "U43") (pin "12") (pinfunction "~{Y0b}_12") (pintype "passive"))
      (node (ref "U47") (pin "1") (pintype "passive"))
    )
    (net (code "97") (name "Net-(U43-~{Y1a})") (class "Default")
      (node (ref "U43") (pin "5") (pinfunction "~{Y1a}_5") (pintype "passive"))
      (node (ref "U47") (pin "11") (pintype "passive"))
    )
    (net (code "98") (name "Net-(U43-~{Y1b})") (class "Default")
      (node (ref "U43") (pin "11") (pinfunction "~{Y1b}_11") (pintype "passive"))
      (node (ref "U47") (pin "3") (pintype "passive"))
    )
    (net (code "99") (name "Net-(U43-~{Y2a})") (class "Default")
      (node (ref "U43") (pin "6") (pinfunction "~{Y2a}_6") (pintype "passive"))
      (node (ref "U47") (pin "9") (pintype "passive"))
    )
    (net (code "100") (name "Net-(U43-~{Y2b})") (class "Default")
      (node (ref "U43") (pin "10") (pinfunction "~{Y2b}_10") (pintype "passive"))
      (node (ref "U47") (pin "5") (pintype "passive"))
    )
    (net (code "101") (name "unconnected-(CR2-Pad2)") (class "Default")
      (node (ref "CR2") (pin "2") (pintype "passive"))
    )
    (net (code "102") (name "unconnected-(CR2-case-Pad3)") (class "Default")
      (node (ref "CR2") (pin "3") (pinfunction "case_3") (pintype "passive"))
    )
    (net (code "103") (name "unconnected-(U3-O2-Pad11)") (class "Default")
      (node (ref "U3") (pin "11") (pinfunction "O2_11") (pintype "passive"))
    )
    (net (code "104") (name "unconnected-(U43-~{Y3a}-Pad7)") (class "Default")
      (node (ref "U43") (pin "7") (pinfunction "~{Y3a}_7") (pintype "passive"))
    )
    (net (code "105") (name "unconnected-(U43-~{Y3b}-Pad9)") (class "Default")
      (node (ref "U43") (pin "9") (pinfunction "~{Y3b}_9") (pintype "passive"))
    )
    (net (code "106") (name "unconnected-(U50A-OUT-Pad6)") (class "Default")
      (node (ref "U50") (pin "6") (pinfunction "OUT_6") (pintype "passive"))
    )
  )
)
